# PX4FMUlite_V0_4.net
KiCad netlist of a schematic drawn in EAGLE
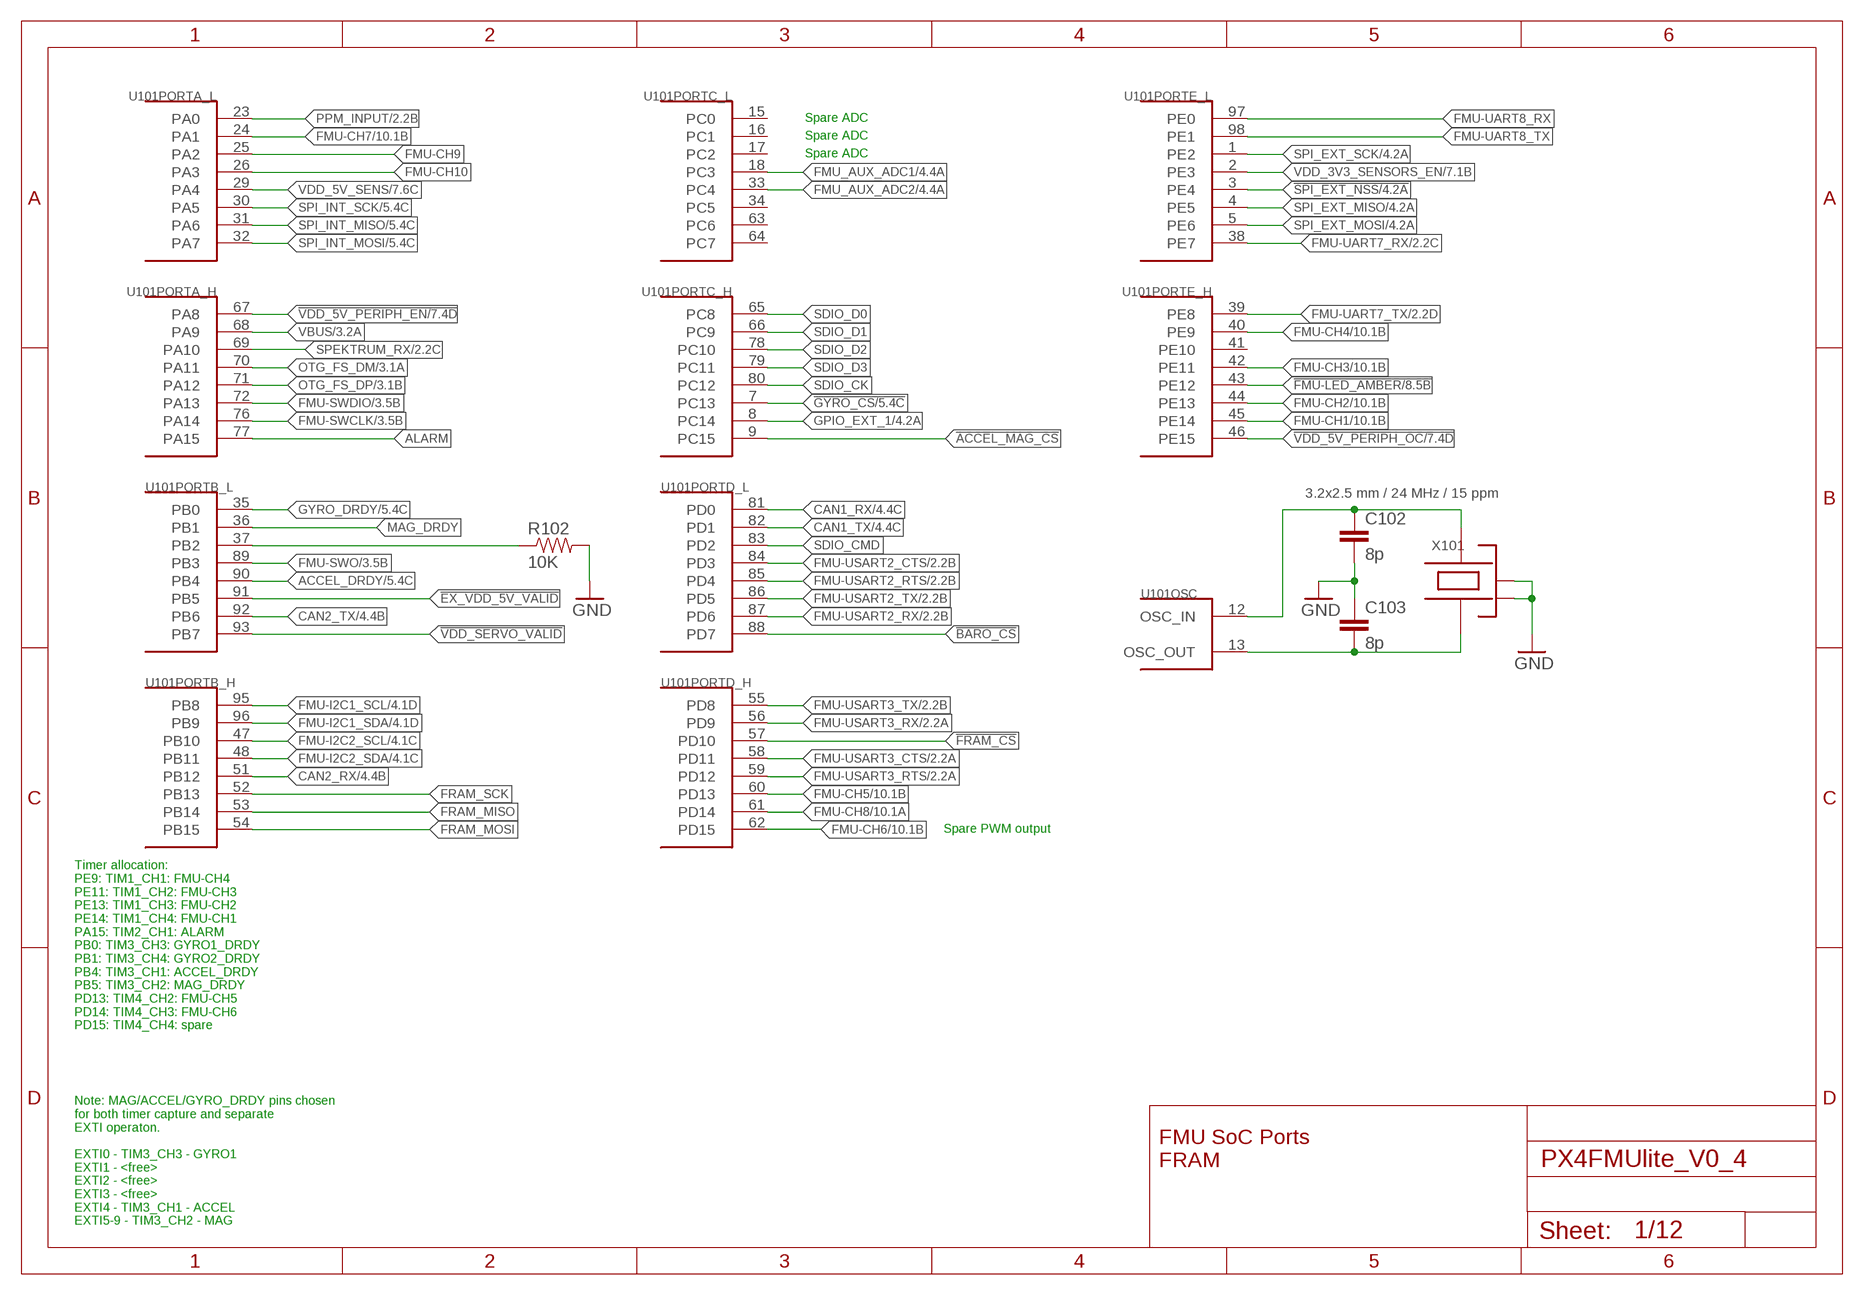
[diagram p0: schematic, sheet 1]
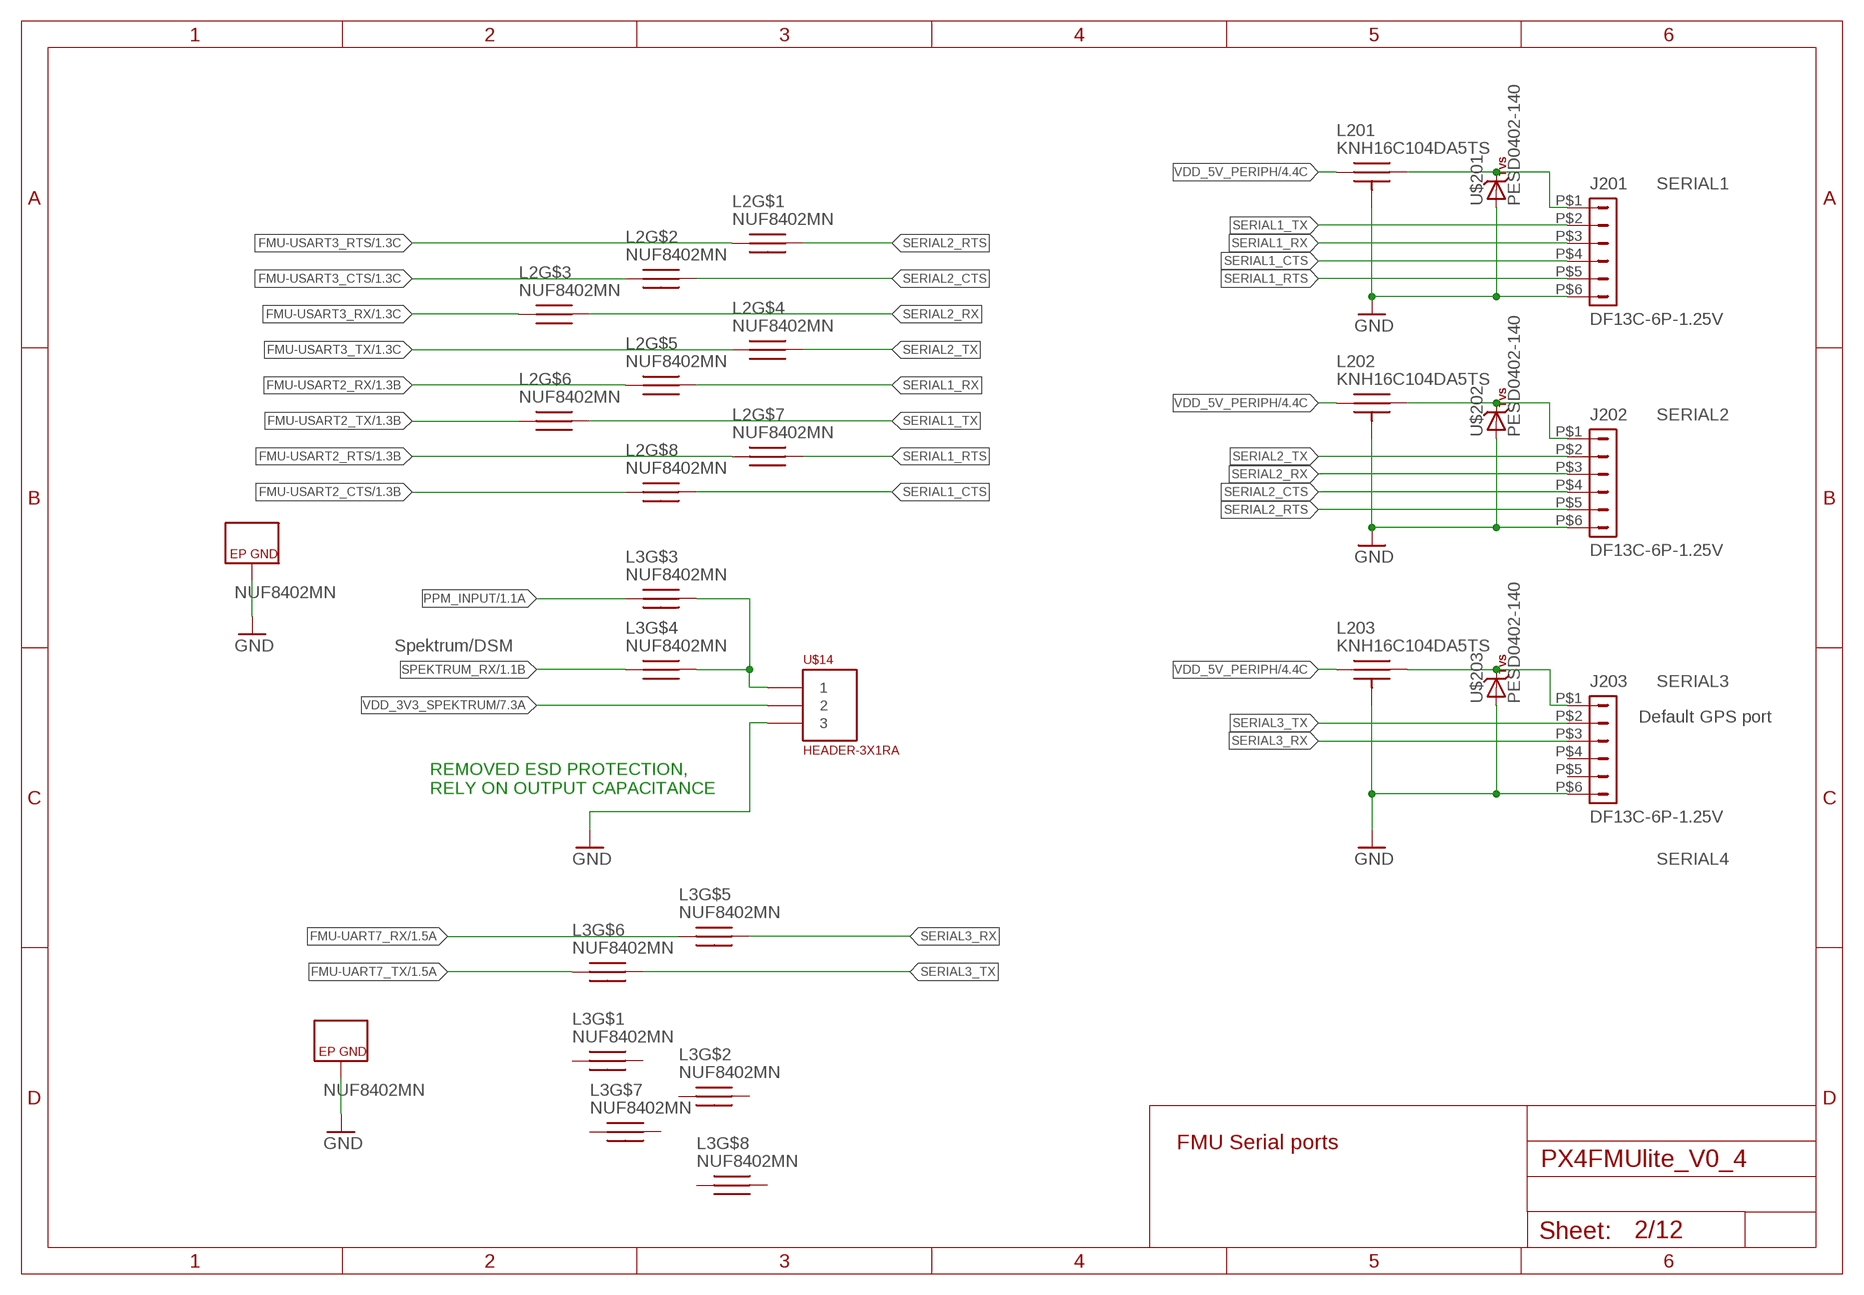
[diagram p1: schematic, sheet 2]
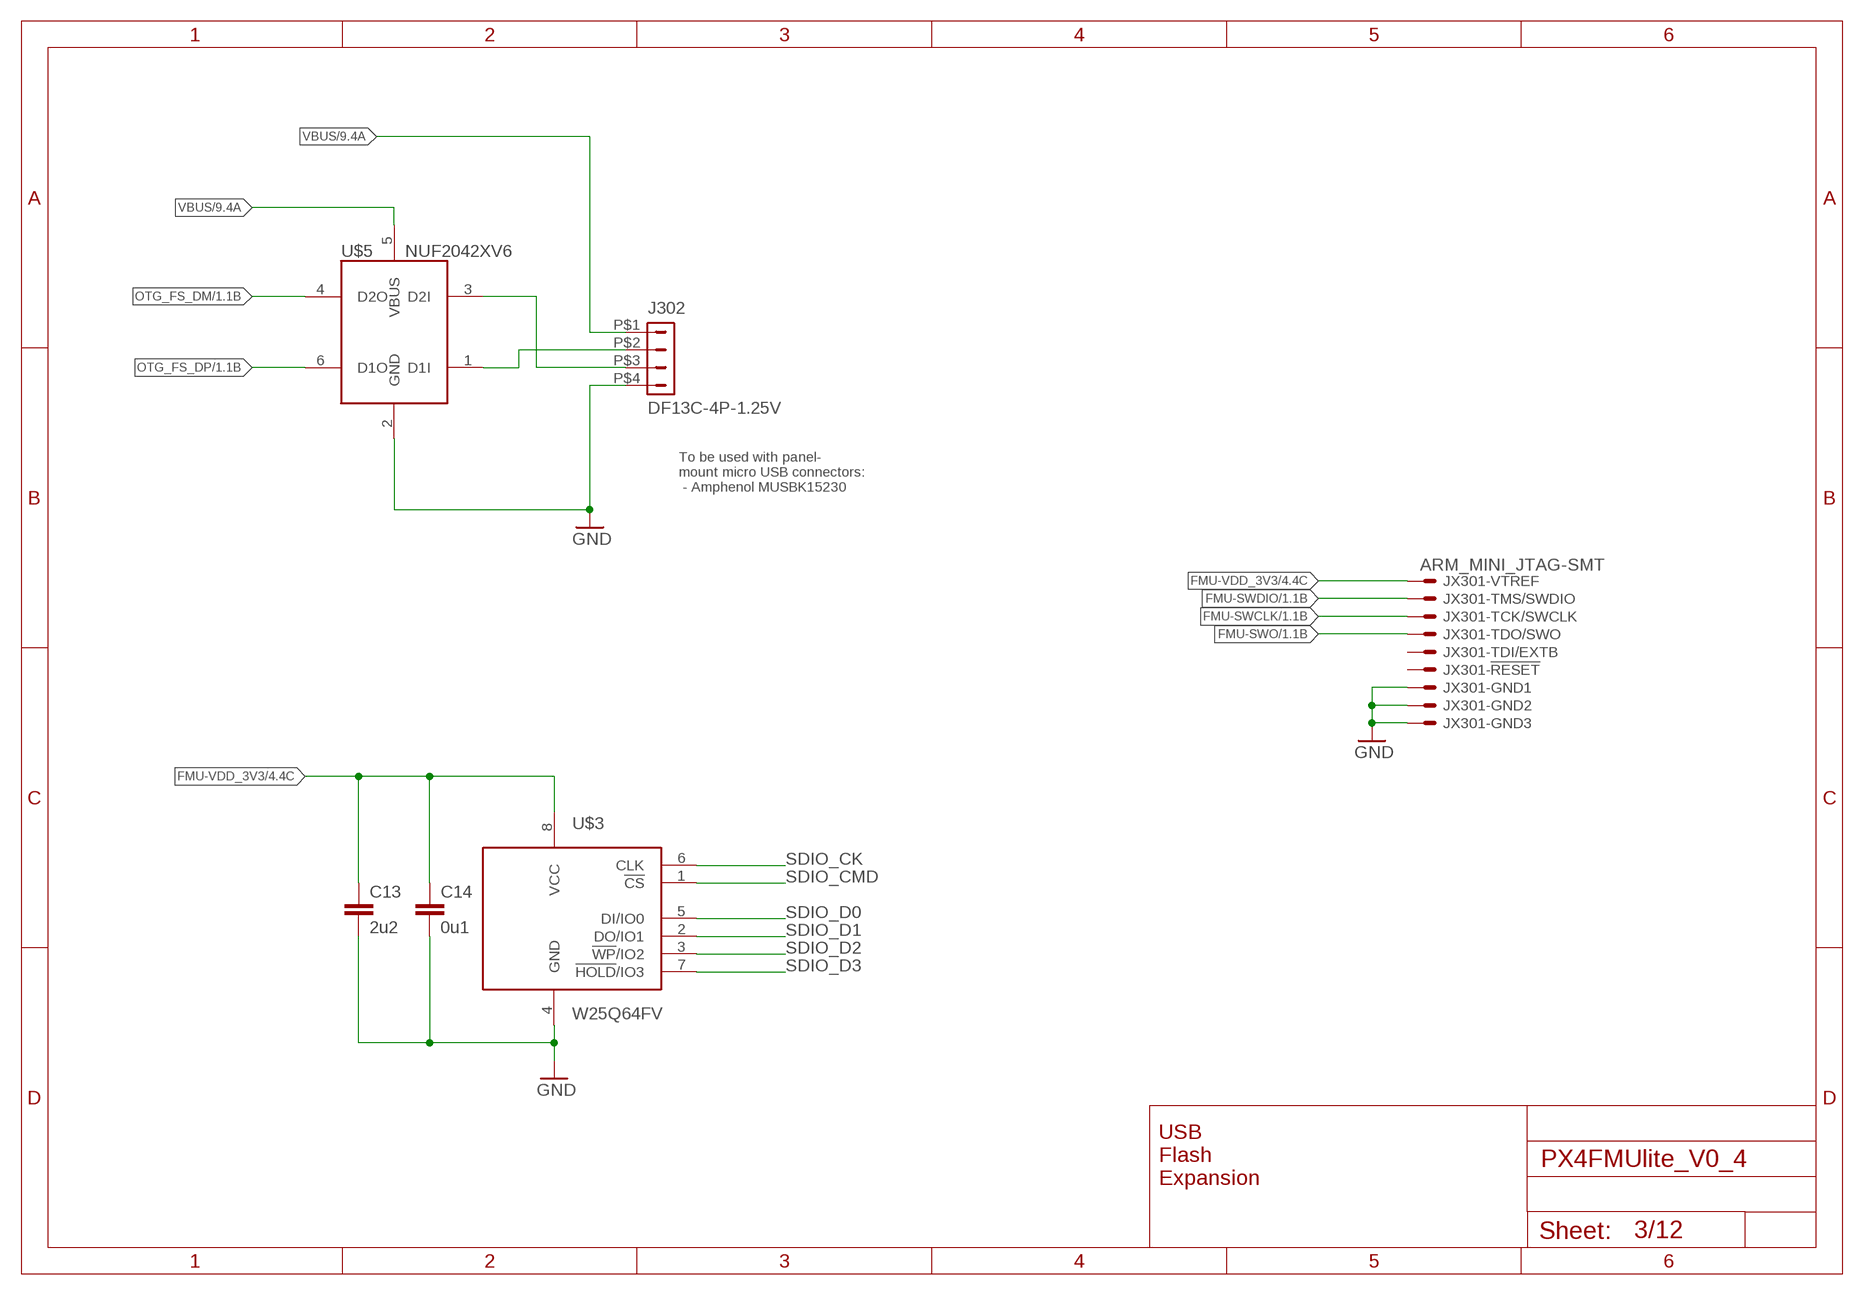
[diagram p2: schematic, sheet 3]
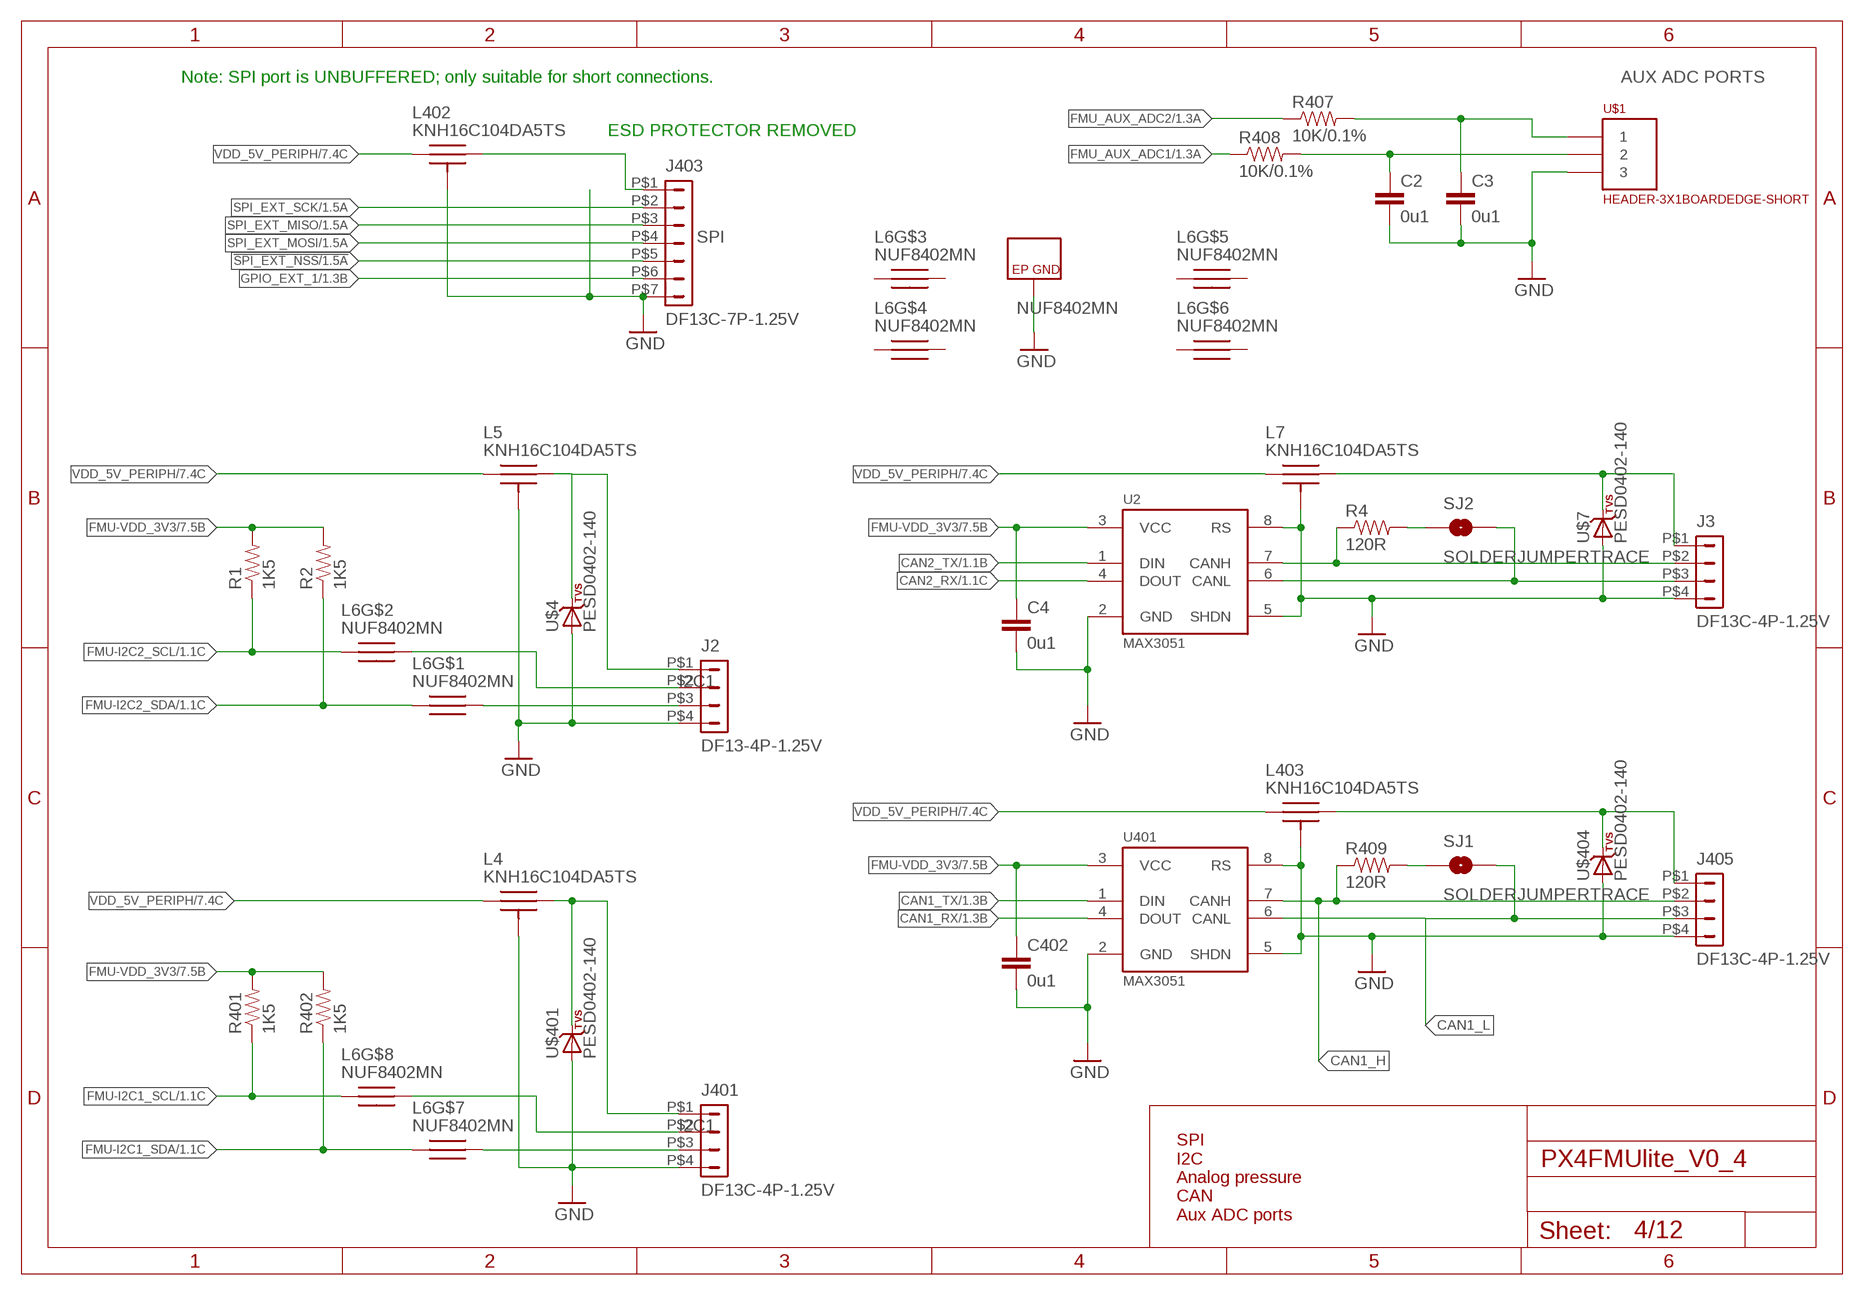
[diagram p3: schematic, sheet 4]
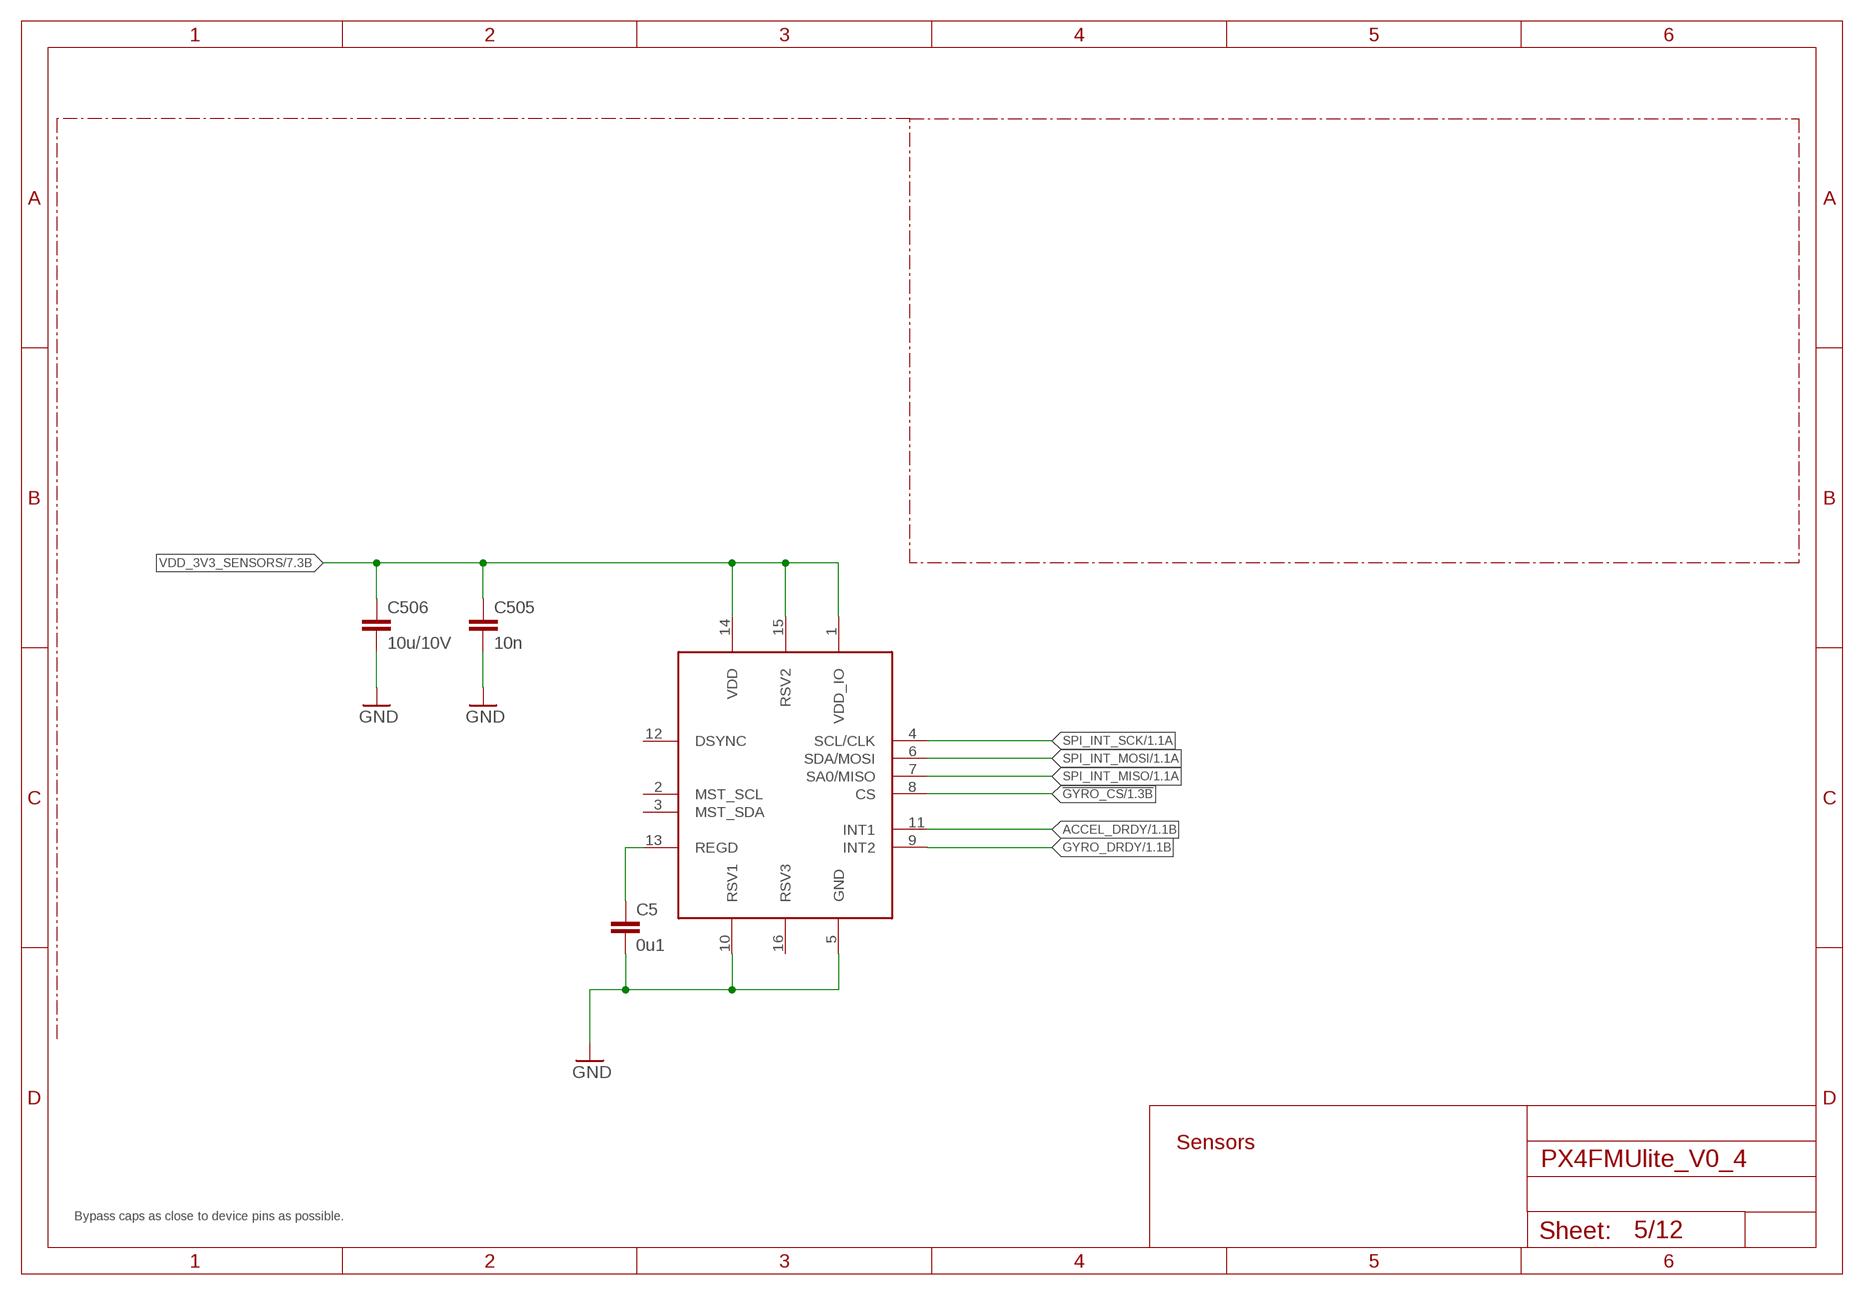
[diagram p4: schematic, sheet 5]
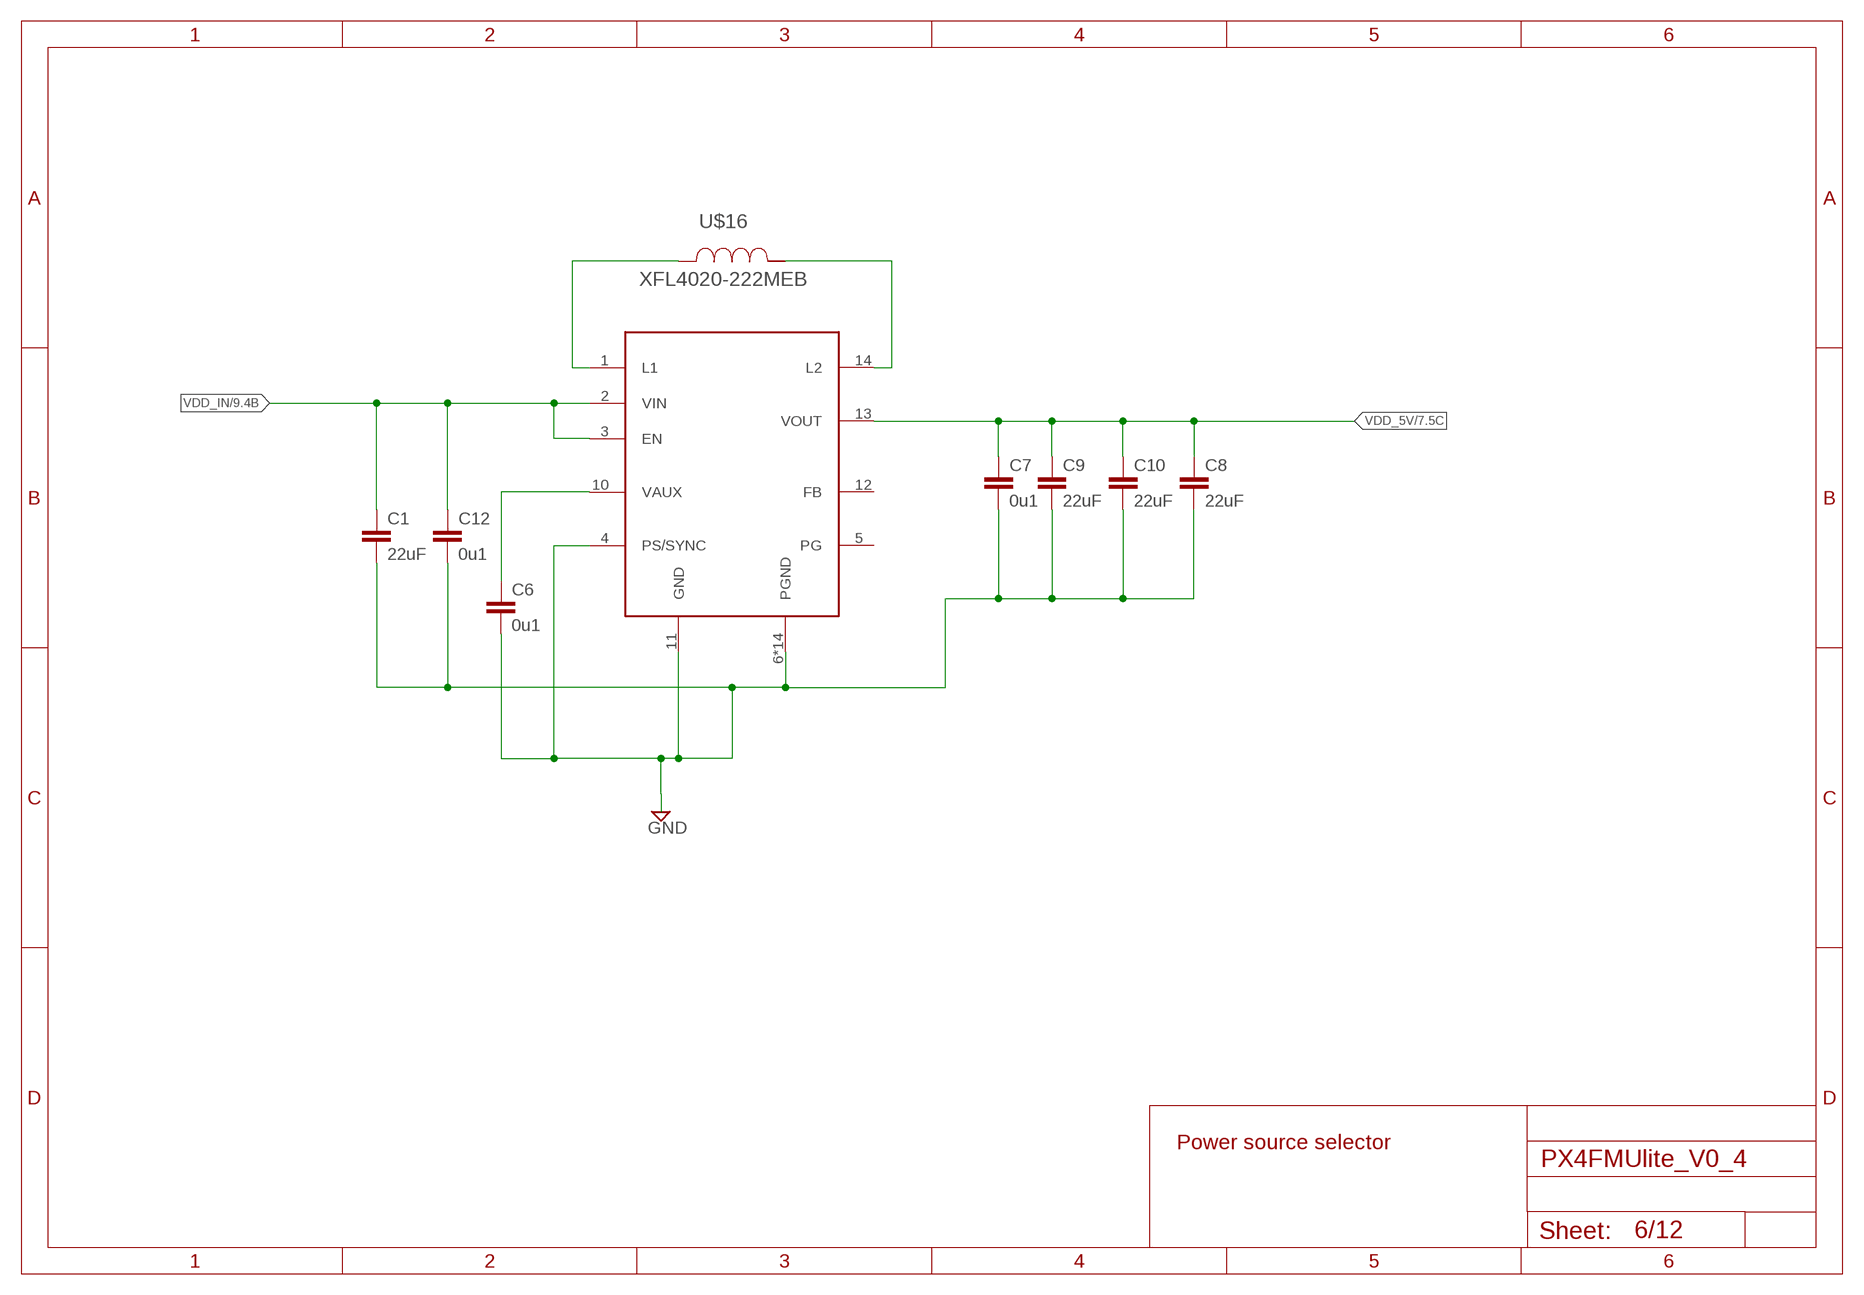
[diagram p5: schematic, sheet 6]
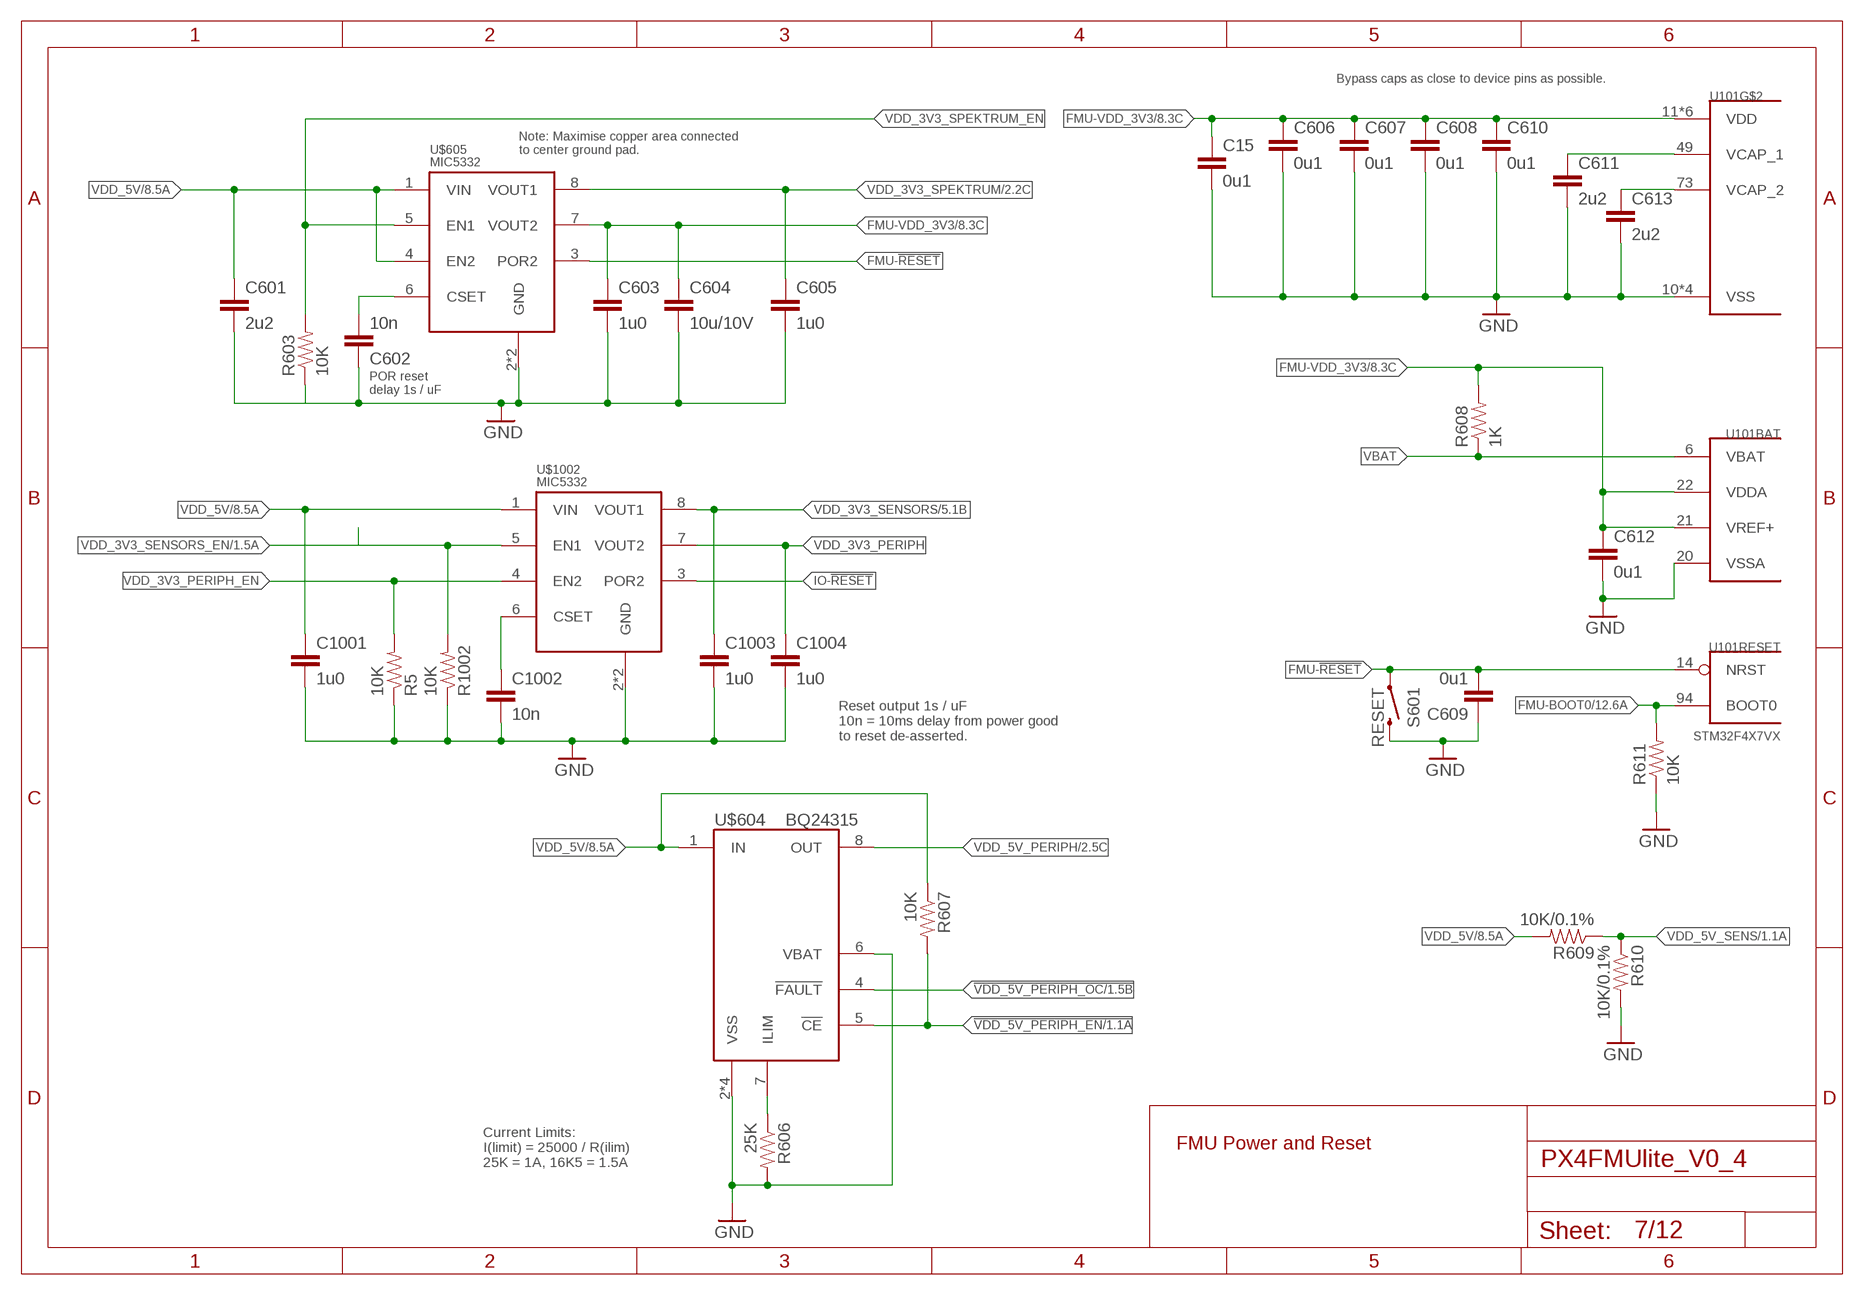
[diagram p6: schematic, sheet 7]
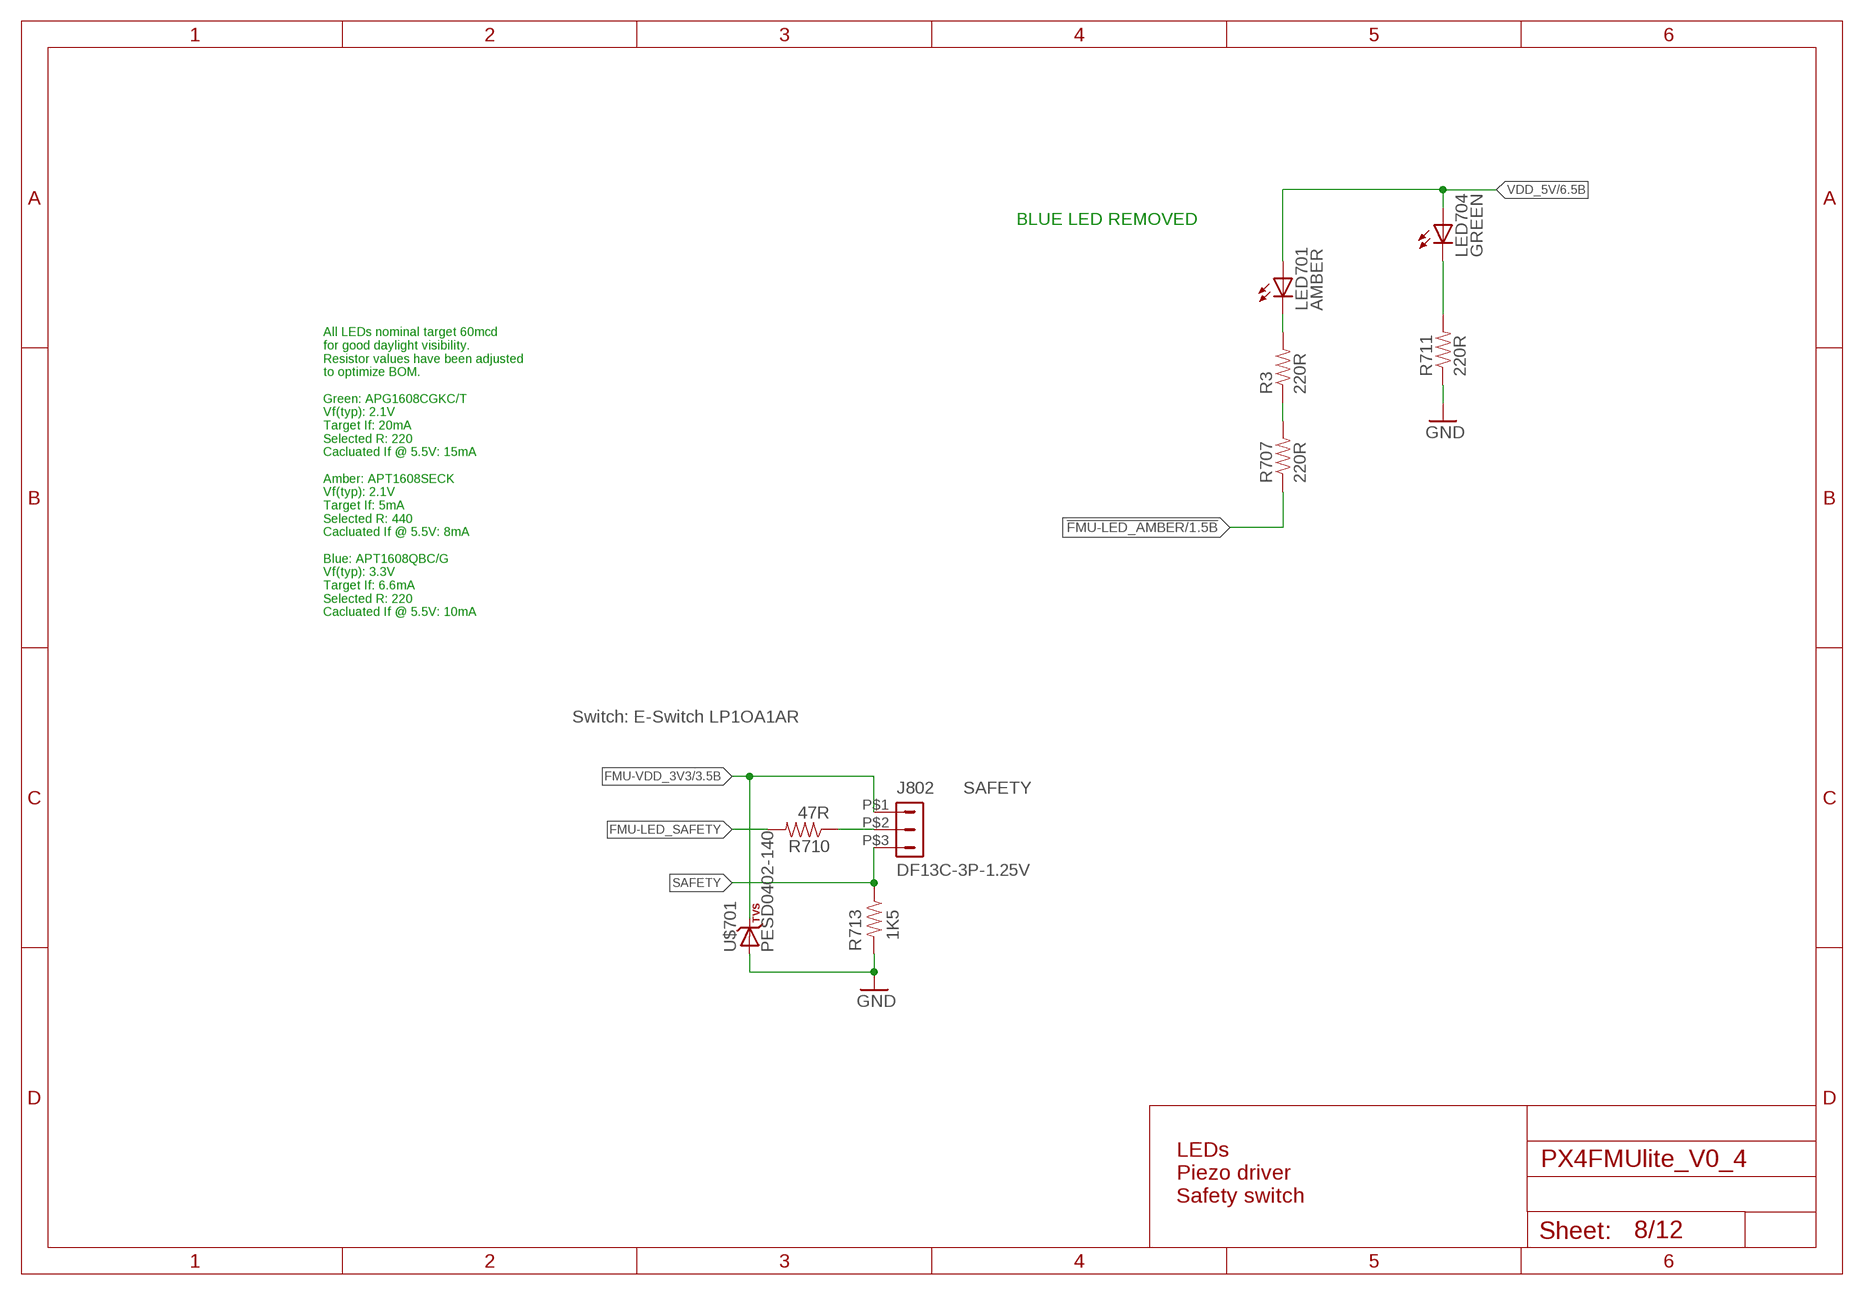
[diagram p7: schematic, sheet 8]
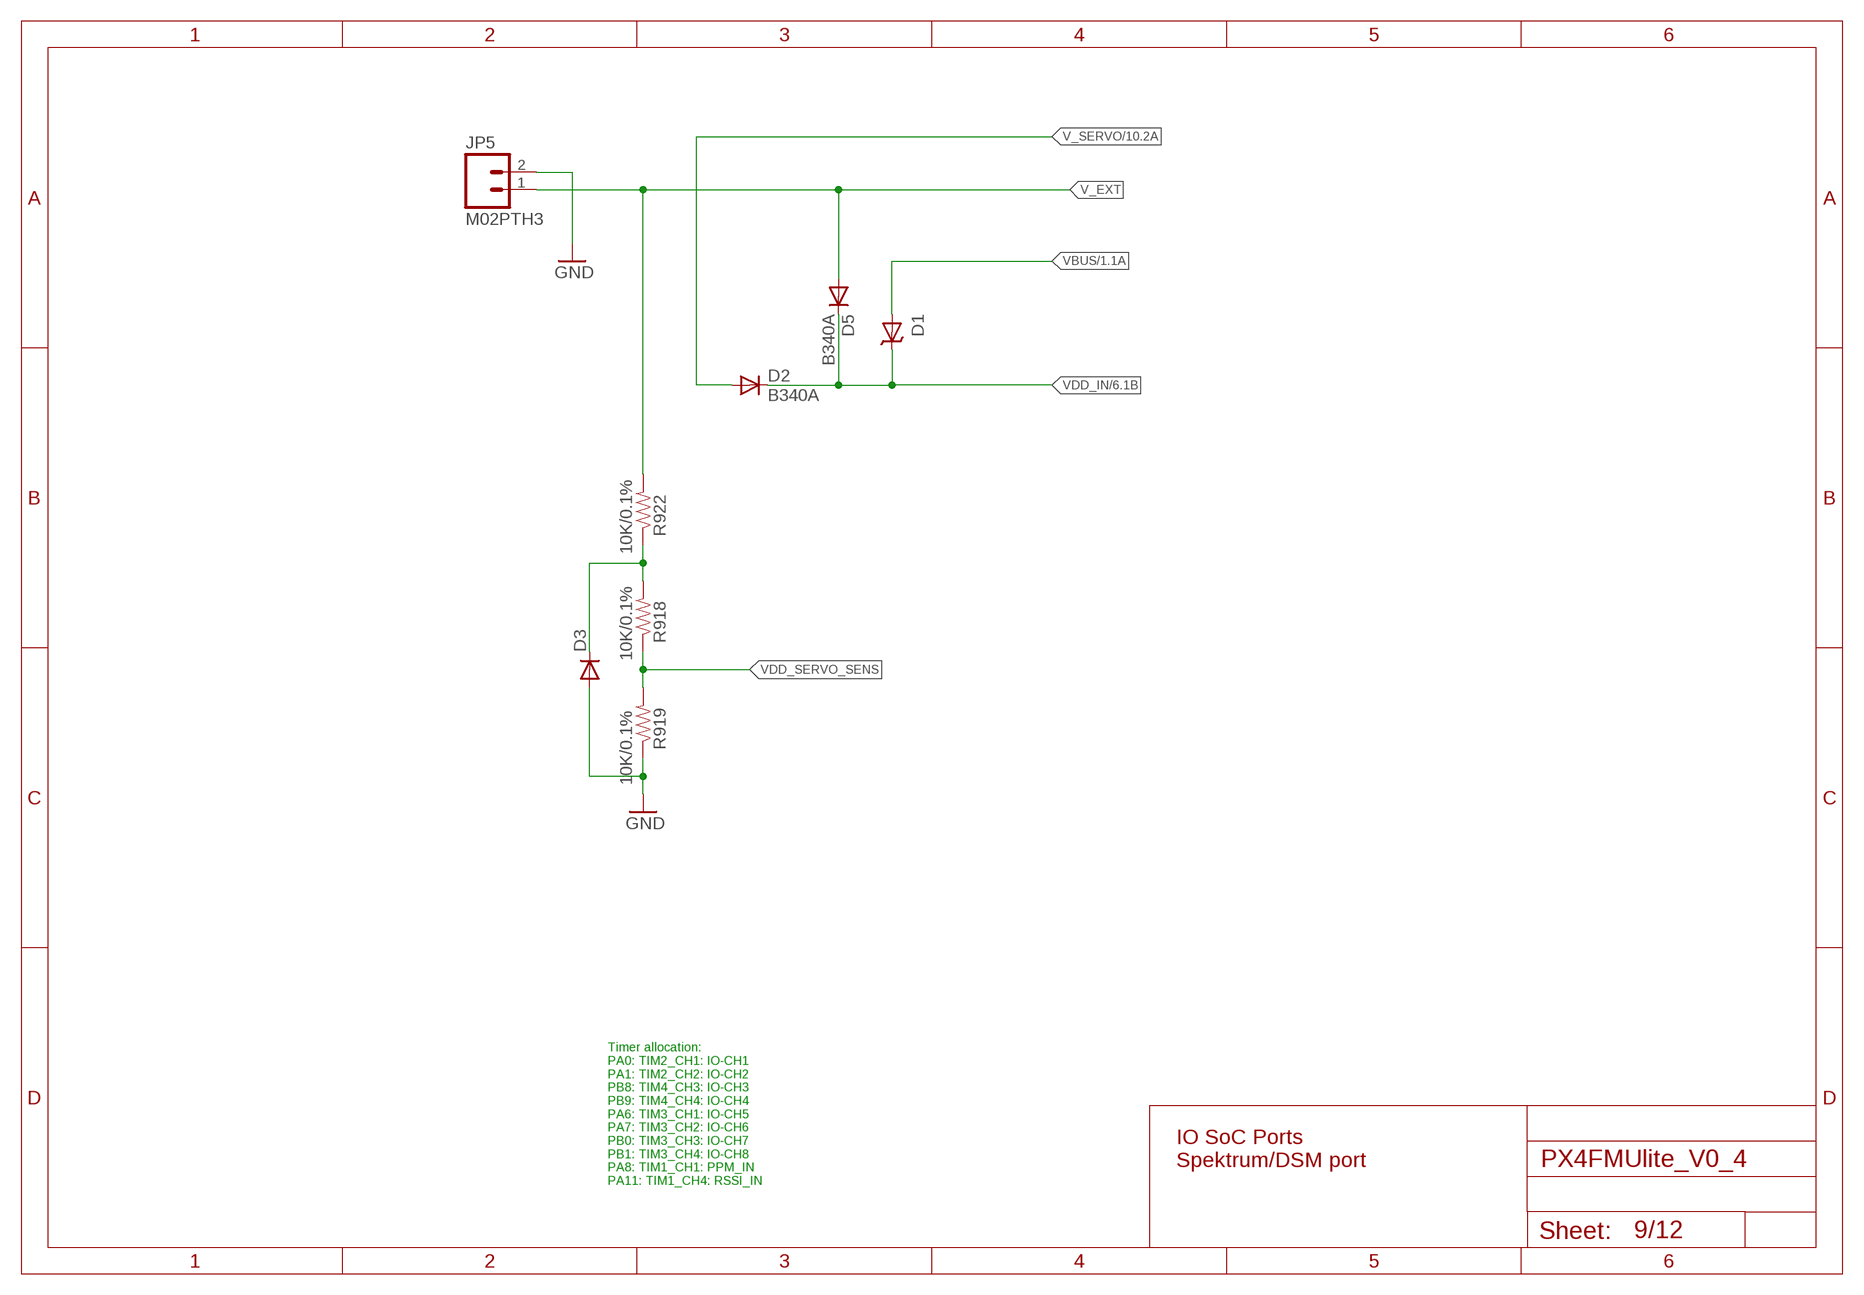
[diagram p8: schematic, sheet 9]
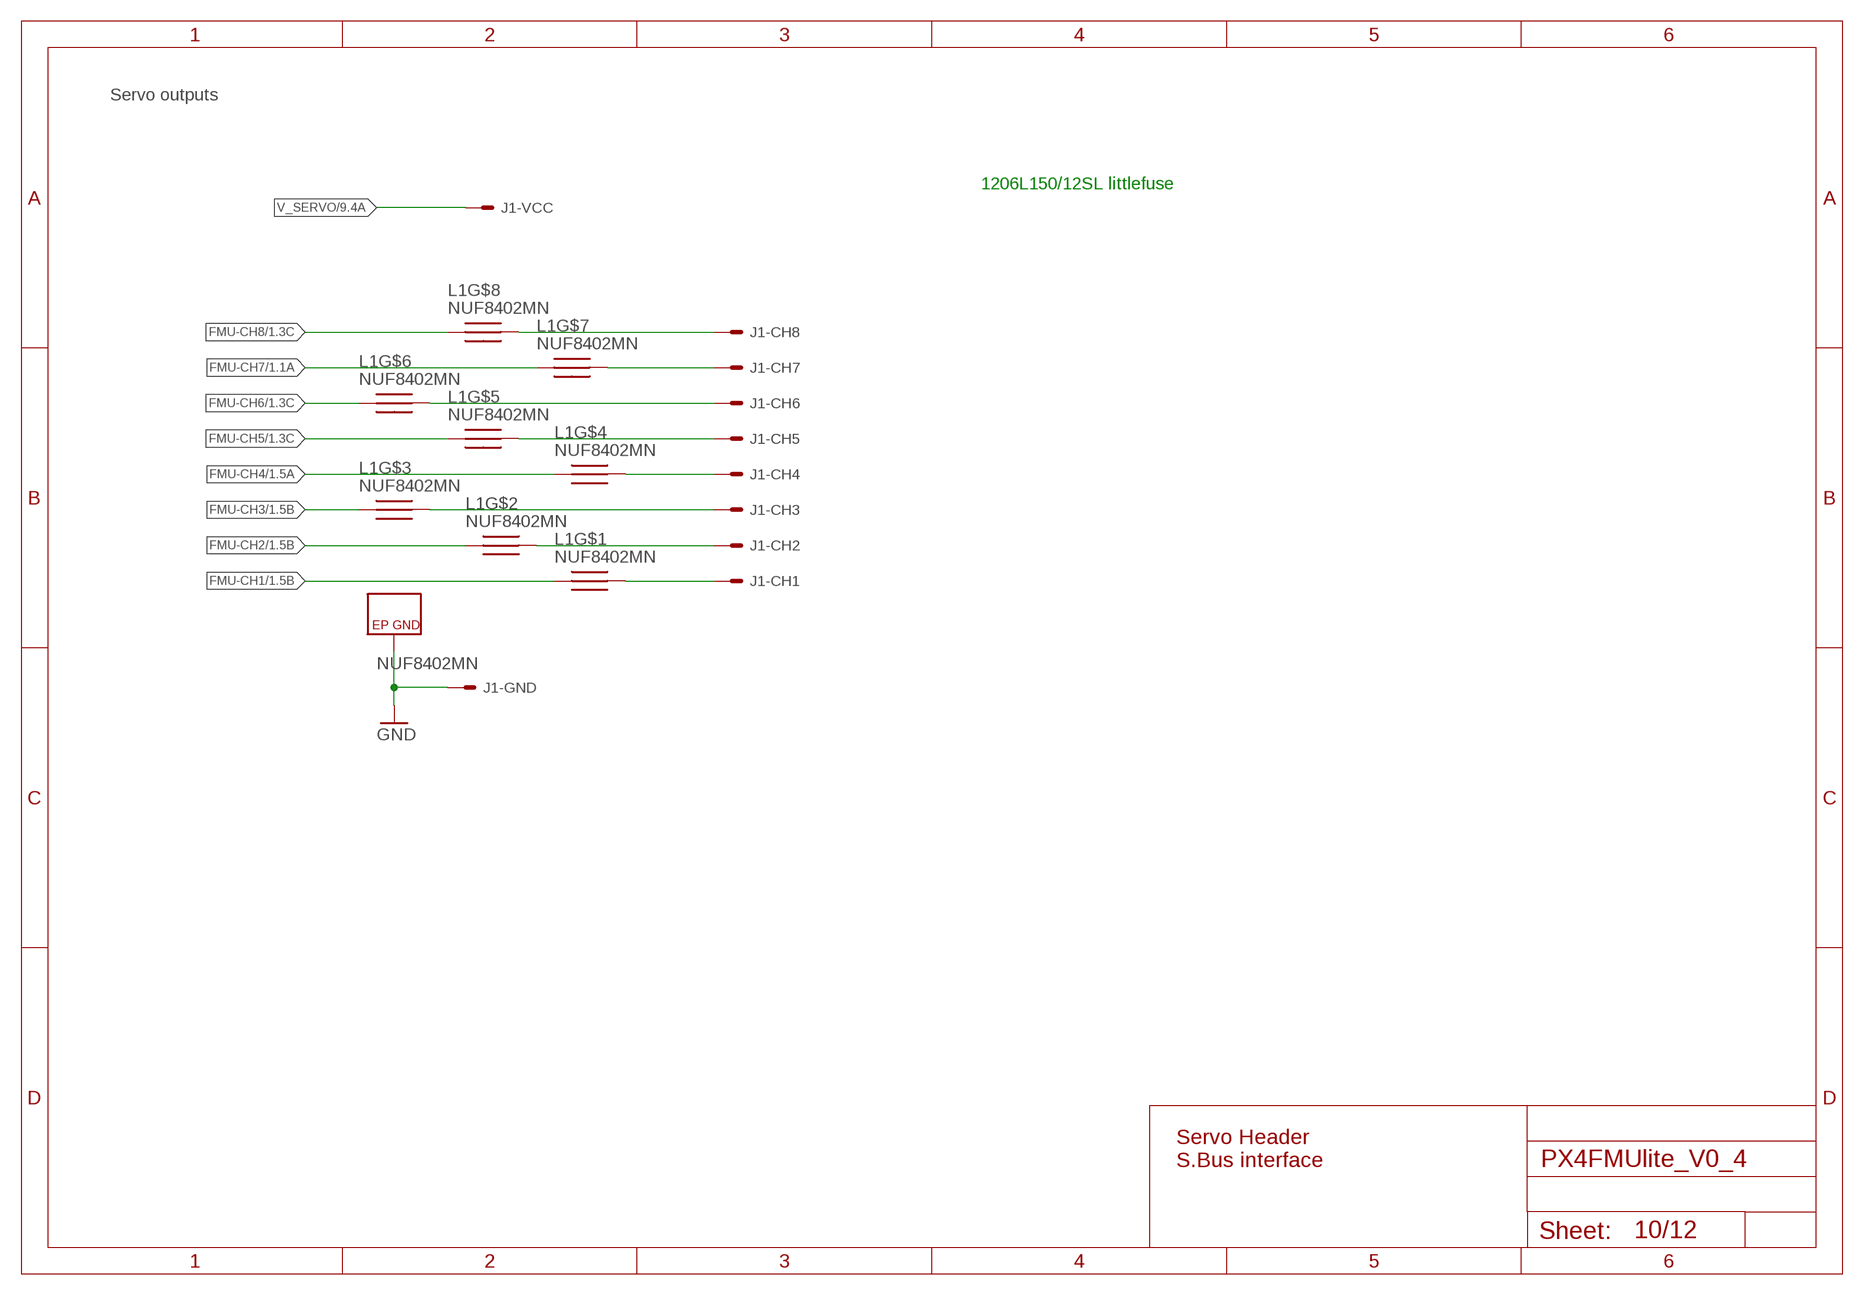
[diagram p9: schematic, sheet 10]
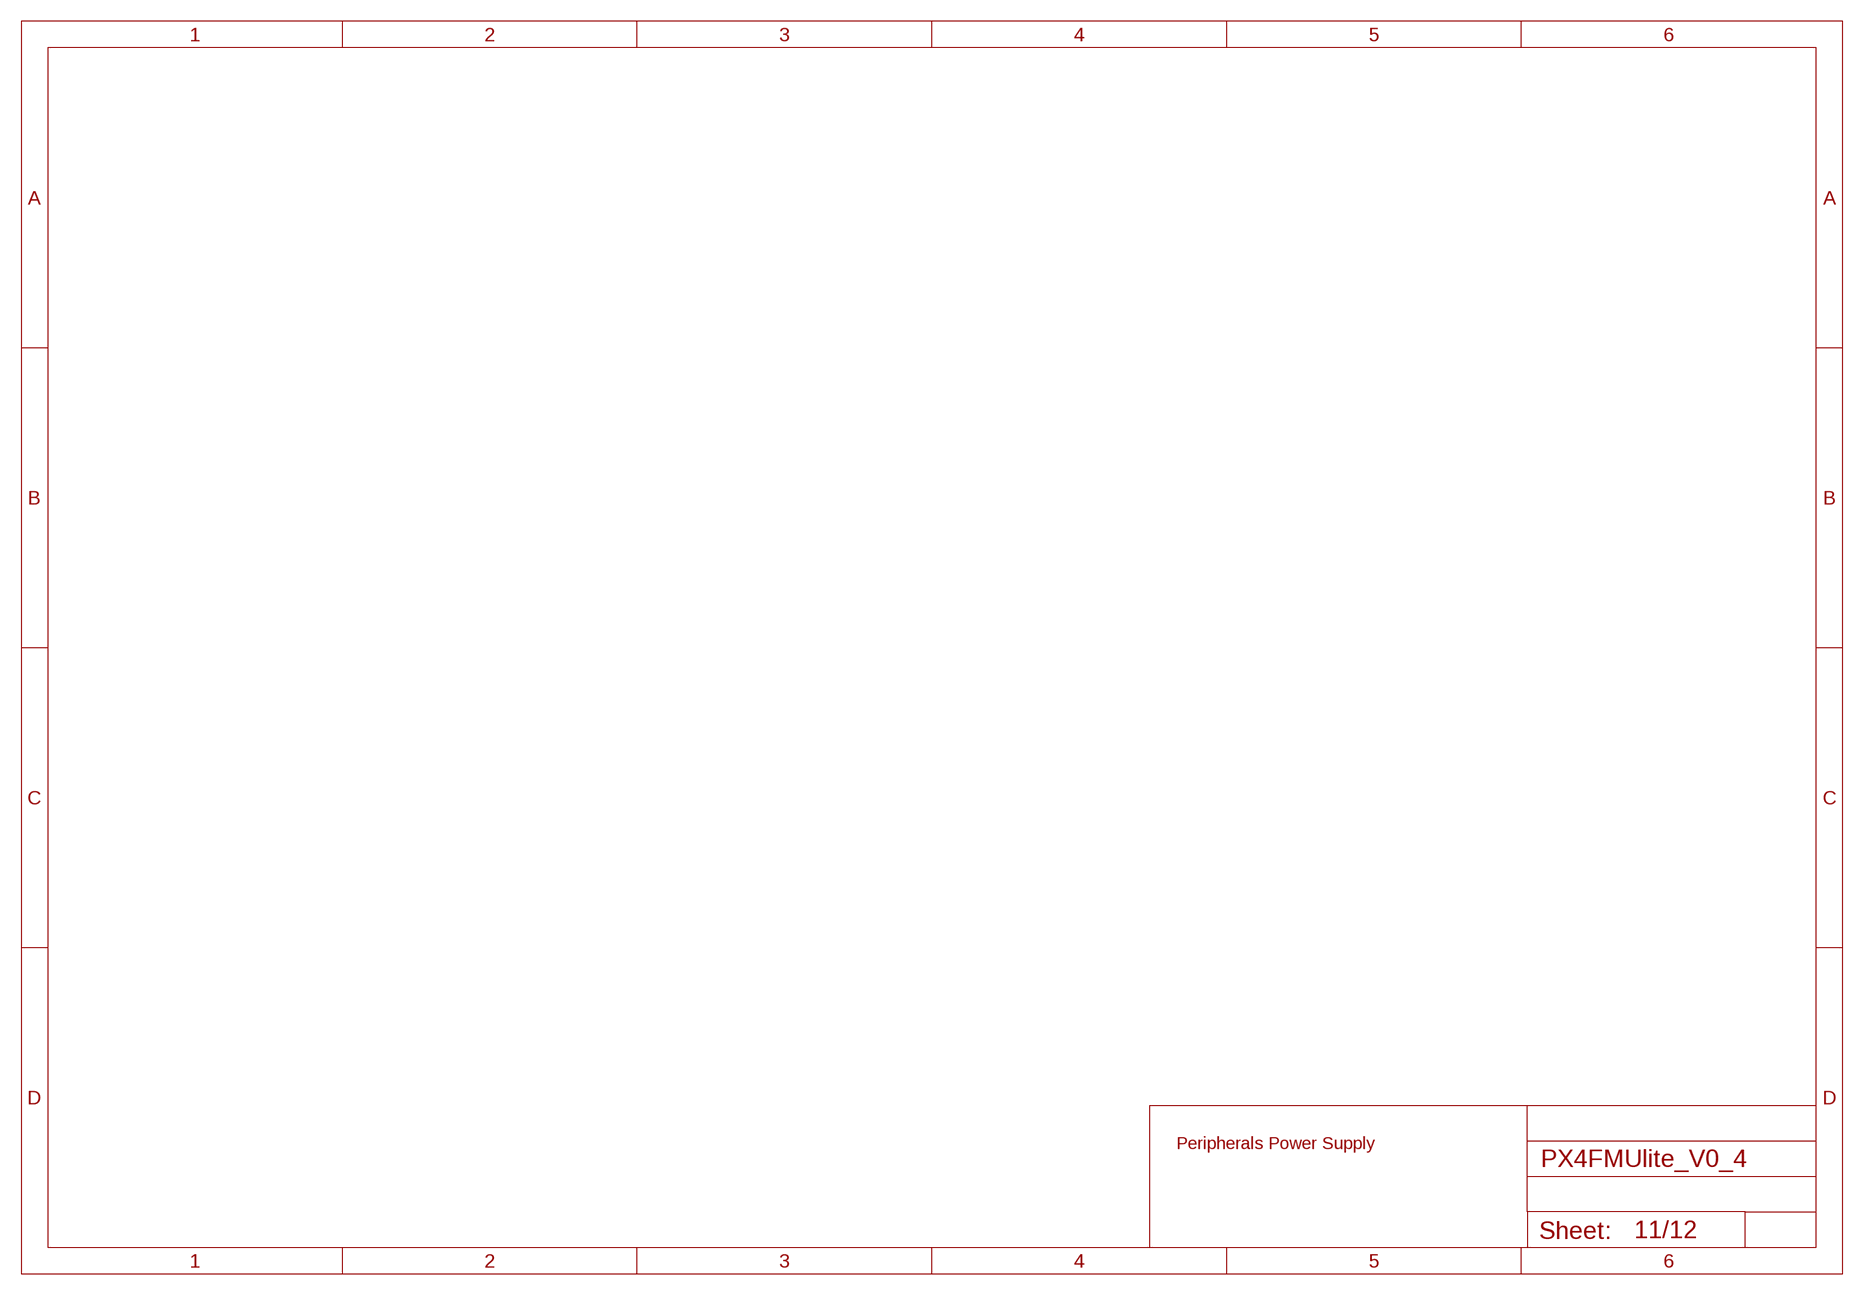
[diagram p10: schematic, sheet 11]
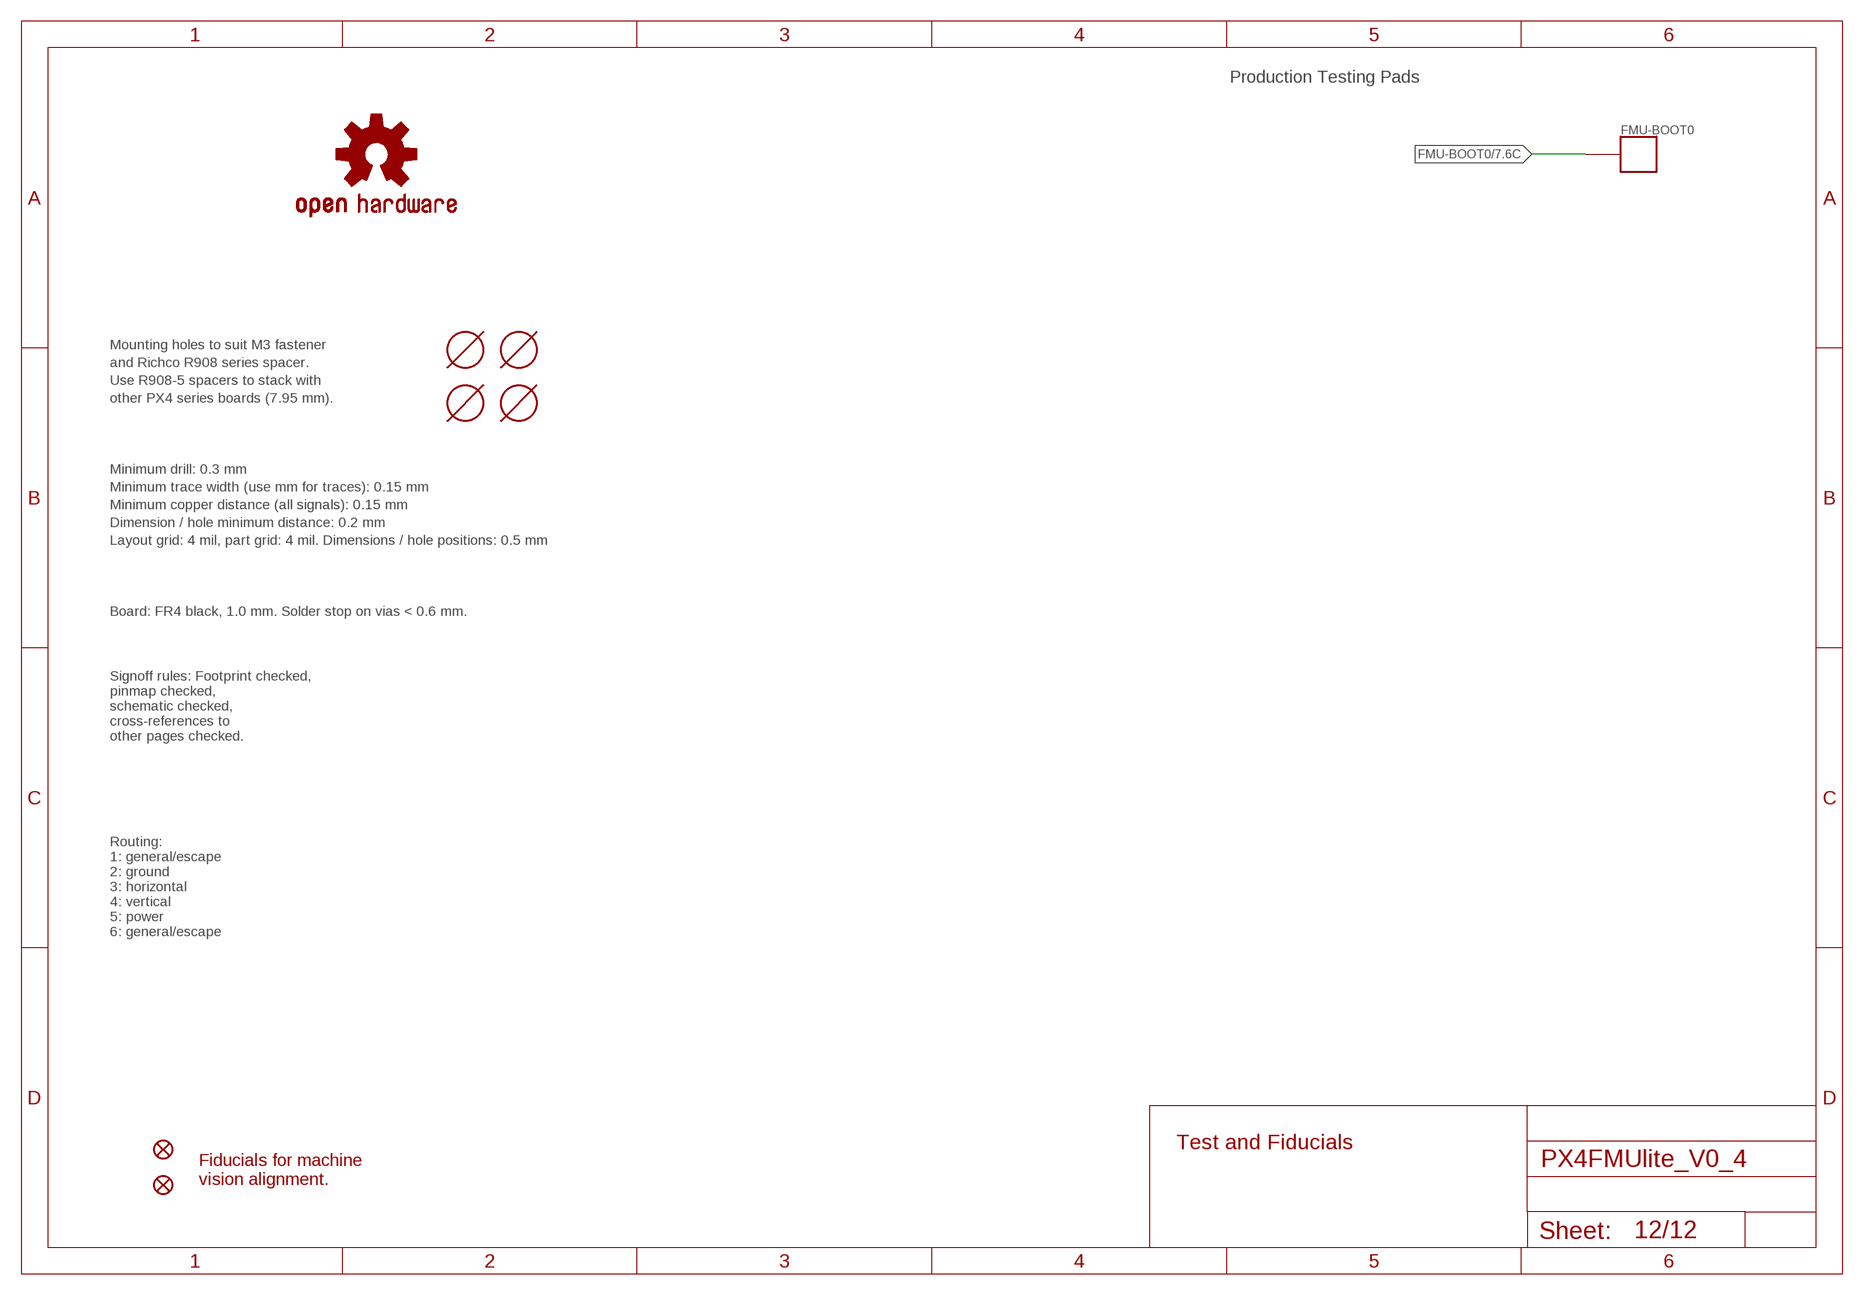
[diagram p11: schematic, sheet 12]

(export (version "E")
  (design (tool "Eeschema 10.0.6"))
  (components
    (comp (ref "J1")
      (value "SERVO_HEADER-3X8")
      (footprint "eagle-import:3X8RA_SERVO")
      (libsource (lib "eagle-import") (part "SERVO_HEADER-3X8"))
    )
    (comp (ref "L1")
      (value "NUF8402MN")
      (footprint "eagle-import:DFN16-THIN")
      (libsource (lib "eagle-import") (part "NUF8402MN"))
    )
    (comp (ref "C15")
      (value "0u1")
      (footprint "eagle-import:0402-CAP")
      (fields (field (name "PARTNO") "CC0402ZRY5V7BB104"))
      (libsource (lib "eagle-import") (part "CAP0402"))
    )
    (comp (ref "C601")
      (value "2u2")
      (footprint "eagle-import:0603-CAP")
      (fields (field (name "PARTNO") "C1608Y5V1C225Z"))
      (libsource (lib "eagle-import") (part "CAP0603"))
    )
    (comp (ref "C602")
      (value "10n")
      (footprint "eagle-import:0402-CAP")
      (fields (field (name "PARTNO") "CC0402KRX7R7BB103"))
      (libsource (lib "eagle-import") (part "CAP0402"))
    )
    (comp (ref "C603")
      (value "1u0")
      (footprint "eagle-import:0603-CAP")
      (fields (field (name "PARTNO") "CC0603ZRY5V7BB105"))
      (libsource (lib "eagle-import") (part "CAP0603"))
    )
    (comp (ref "C604")
      (value "10u/10V")
      (footprint "eagle-import:0805-CAP")
      (fields (field (name "PARTNO") "CC0805ZKY5V6BB106"))
      (libsource (lib "eagle-import") (part "CAP0805"))
    )
    (comp (ref "C605")
      (value "1u0")
      (footprint "eagle-import:0603-CAP")
      (fields (field (name "PARTNO") "CC0603ZRY5V7BB105"))
      (libsource (lib "eagle-import") (part "CAP0603"))
    )
    (comp (ref "C606")
      (value "0u1")
      (footprint "eagle-import:0402-CAP")
      (fields (field (name "PARTNO") "CC0402ZRY5V7BB104"))
      (libsource (lib "eagle-import") (part "CAP0402"))
    )
    (comp (ref "C607")
      (value "0u1")
      (footprint "eagle-import:0402-CAP")
      (fields (field (name "PARTNO") "CC0402ZRY5V7BB104"))
      (libsource (lib "eagle-import") (part "CAP0402"))
    )
    (comp (ref "C608")
      (value "0u1")
      (footprint "eagle-import:0402-CAP")
      (fields (field (name "PARTNO") "CC0402ZRY5V7BB104"))
      (libsource (lib "eagle-import") (part "CAP0402"))
    )
    (comp (ref "C609")
      (value "0u1")
      (footprint "eagle-import:0402-CAP")
      (fields (field (name "PARTNO") "CC0402ZRY5V7BB104"))
      (libsource (lib "eagle-import") (part "CAP0402"))
    )
    (comp (ref "C610")
      (value "0u1")
      (footprint "eagle-import:0402-CAP")
      (fields (field (name "PARTNO") "CC0402ZRY5V7BB104"))
      (libsource (lib "eagle-import") (part "CAP0402"))
    )
    (comp (ref "C611")
      (value "2u2")
      (footprint "eagle-import:0603-CAP")
      (fields (field (name "PARTNO") "C1608Y5V1C225Z"))
      (libsource (lib "eagle-import") (part "CAP0603"))
    )
    (comp (ref "C612")
      (value "0u1")
      (footprint "eagle-import:0402-CAP")
      (fields (field (name "PARTNO") "CC0402ZRY5V7BB104"))
      (libsource (lib "eagle-import") (part "CAP0402"))
    )
    (comp (ref "C613")
      (value "2u2")
      (footprint "eagle-import:0603-CAP")
      (fields (field (name "PARTNO") "C1608Y5V1C225Z"))
      (libsource (lib "eagle-import") (part "CAP0603"))
    )
    (comp (ref "C1001")
      (value "1u0")
      (footprint "eagle-import:0603-CAP")
      (fields (field (name "PARTNO") "CC0603ZRY5V7BB105"))
      (libsource (lib "eagle-import") (part "CAP0603"))
    )
    (comp (ref "C1002")
      (value "10n")
      (footprint "eagle-import:0402-CAP")
      (fields (field (name "PARTNO") "CC0402KRX7R7BB103"))
      (libsource (lib "eagle-import") (part "CAP0402"))
    )
    (comp (ref "C1003")
      (value "1u0")
      (footprint "eagle-import:0603-CAP")
      (fields (field (name "PARTNO") "CC0603ZRY5V7BB105"))
      (libsource (lib "eagle-import") (part "CAP0603"))
    )
    (comp (ref "C1004")
      (value "1u0")
      (footprint "eagle-import:0603-CAP")
      (fields (field (name "PARTNO") "CC0603ZRY5V7BB105"))
      (libsource (lib "eagle-import") (part "CAP0603"))
    )
    (comp (ref "R5")
      (value "10K")
      (footprint "eagle-import:0402-RES")
      (fields (field (name "PARTNO") "RC0402FR-0710KL"))
      (libsource (lib "eagle-import") (part "RESISTOR0402-RES"))
    )
    (comp (ref "R603")
      (value "10K")
      (footprint "eagle-import:0402-RES")
      (fields (field (name "PARTNO") "RC0402FR-0710KL"))
      (libsource (lib "eagle-import") (part "RESISTOR0402-RES"))
    )
    (comp (ref "R606")
      (value "25K")
      (footprint "eagle-import:0402-RES")
      (fields (field (name "PARTNO") "RMCF0402FT25K5"))
      (libsource (lib "eagle-import") (part "RESISTOR0402-RES"))
    )
    (comp (ref "R607")
      (value "10K")
      (footprint "eagle-import:0402-RES")
      (fields (field (name "PARTNO") "RC0402FR-0710KL"))
      (libsource (lib "eagle-import") (part "RESISTOR0402-RES"))
    )
    (comp (ref "R608")
      (value "1K")
      (footprint "eagle-import:0402-RES")
      (fields (field (name "PARTNO") "RC0402FR-071KL"))
      (libsource (lib "eagle-import") (part "RESISTOR0402-RES"))
    )
    (comp (ref "R609")
      (value "10K/0.1%")
      (footprint "eagle-import:0402-RES")
      (fields (field (name "PARTNO") "ERA-2AEB103X"))
      (libsource (lib "eagle-import") (part "RESISTOR0402-RES"))
    )
    (comp (ref "R610")
      (value "10K/0.1%")
      (footprint "eagle-import:0402-RES")
      (fields (field (name "PARTNO") "ERA-2AEB103X"))
      (libsource (lib "eagle-import") (part "RESISTOR0402-RES"))
    )
    (comp (ref "R611")
      (value "10K")
      (footprint "eagle-import:0402-RES")
      (fields (field (name "PARTNO") "RC0402FR-0710KL"))
      (libsource (lib "eagle-import") (part "RESISTOR0402-RES"))
    )
    (comp (ref "R1002")
      (value "10K")
      (footprint "eagle-import:0402-RES")
      (fields (field (name "PARTNO") "RC0402FR-0710KL"))
      (libsource (lib "eagle-import") (part "RESISTOR0402-RES"))
    )
    (comp (ref "S601")
      (value "RESET")
      (footprint "eagle-import:EVQP7J01K")
      (fields (field (name "PARTNO") "EVQP7J01K"))
      (libsource (lib "eagle-import") (part "SWITCH-MOMENTARY-2"))
    )
    (comp (ref "U$604")
      (value "BQ24315")
      (footprint "eagle-import:QFN8-DSG")
      (fields (field (name "PARTNO") "BQ24315DSGR"))
      (libsource (lib "eagle-import") (part "BQ24315"))
    )
    (comp (ref "U$605")
      (value "MIC5332")
      (footprint "eagle-import:MLF-8-EPAD")
      (fields (field (name "PARTNO") "MIC5332-SSYMT"))
      (libsource (lib "eagle-import") (part "MIC5332"))
    )
    (comp (ref "U$1002")
      (value "MIC5332")
      (footprint "eagle-import:MLF-8-EPAD")
      (fields (field (name "PARTNO") "MIC5332-SSYMT"))
      (libsource (lib "eagle-import") (part "MIC5332"))
    )
    (comp (ref "U101")
      (value "STM32F4X7VX")
      (footprint "eagle-import:TQFP100")
      (fields (field (name "PARTNO") "STM32F427VI"))
      (libsource (lib "eagle-import") (part "STM32F4X7VX"))
    )
    (comp (ref "FMU-BOOT0")
      (value "PAD.04")
      (footprint "eagle-import:PAD.04X.04")
      (libsource (lib "eagle-import") (part "PAD.04"))
    )
    (comp (ref "JP1")
      (value "FIDUCIAL1.5X3")
      (footprint "eagle-import:FIDUCIAL-1.5X3")
      (libsource (lib "eagle-import") (part "FIDUCIAL1.5X3"))
    )
    (comp (ref "JP2")
      (value "FIDUCIAL1.5X3")
      (footprint "eagle-import:FIDUCIAL-1.5X3")
      (libsource (lib "eagle-import") (part "FIDUCIAL1.5X3"))
    )
    (comp (ref "M3_MOUNT1101")
      (value "MOUNT-HOLE3.1MM")
      (footprint "eagle-import:MOUNT-HOLE3.1")
      (libsource (lib "eagle-import") (part "MOUNT-HOLE3.1MM"))
    )
    (comp (ref "M3_MOUNT1102")
      (value "MOUNT-HOLE3.1MM")
      (footprint "eagle-import:MOUNT-HOLE3.1")
      (libsource (lib "eagle-import") (part "MOUNT-HOLE3.1MM"))
    )
    (comp (ref "M3_MOUNT1103")
      (value "MOUNT-HOLE3.1MM")
      (footprint "eagle-import:MOUNT-HOLE3.1")
      (libsource (lib "eagle-import") (part "MOUNT-HOLE3.1MM"))
    )
    (comp (ref "M3_MOUNT1104")
      (value "MOUNT-HOLE3.1MM")
      (footprint "eagle-import:MOUNT-HOLE3.1")
      (libsource (lib "eagle-import") (part "MOUNT-HOLE3.1MM"))
    )
    (comp (ref "OSHW_LOGO")
      (value "OSHW-LOGOS")
      (footprint "eagle-import:OSHW-LOGO-S")
      (libsource (lib "eagle-import") (part "OSHW-LOGOS"))
    )
    (comp (ref "J201")
      (value "DF13C-6P-1.25V")
      (footprint "eagle-import:DF13C-6P-1.25V")
      (fields (field (name "PARTNO") "DF13C-6P-1.25V(20)"))
      (libsource (lib "eagle-import") (part "DF13-6P-1.25V"))
    )
    (comp (ref "J202")
      (value "DF13C-6P-1.25V")
      (footprint "eagle-import:DF13C-6P-1.25V")
      (fields (field (name "PARTNO") "DF13C-6P-1.25V(20)"))
      (libsource (lib "eagle-import") (part "DF13-6P-1.25V"))
    )
    (comp (ref "J203")
      (value "DF13C-6P-1.25V")
      (footprint "eagle-import:DF13C-6P-1.25V")
      (fields (field (name "PARTNO") "DF13C-6P-1.25V(20)"))
      (libsource (lib "eagle-import") (part "DF13-6P-1.25V"))
    )
    (comp (ref "L2")
      (value "NUF8402MN")
      (footprint "eagle-import:DFN16-THIN")
      (libsource (lib "eagle-import") (part "NUF8402MN"))
    )
    (comp (ref "L3")
      (value "NUF8402MN")
      (footprint "eagle-import:DFN16-THIN")
      (libsource (lib "eagle-import") (part "NUF8402MN"))
    )
    (comp (ref "L201")
      (value "KNH16C104DA5TS")
      (footprint "eagle-import:KYOCERA-KNH16-DA")
      (libsource (lib "eagle-import") (part "KNH16C104DA5TS"))
    )
    (comp (ref "L202")
      (value "KNH16C104DA5TS")
      (footprint "eagle-import:KYOCERA-KNH16-DA")
      (libsource (lib "eagle-import") (part "KNH16C104DA5TS"))
    )
    (comp (ref "L203")
      (value "KNH16C104DA5TS")
      (footprint "eagle-import:KYOCERA-KNH16-DA")
      (libsource (lib "eagle-import") (part "KNH16C104DA5TS"))
    )
    (comp (ref "U$14")
      (value "HEADER-3X1RA")
      (footprint "eagle-import:3X1RA")
      (libsource (lib "eagle-import") (part "HEADER-3X1RA"))
    )
    (comp (ref "U$201")
      (value "PESD0402-140")
      (footprint "eagle-import:0402-TVS")
      (libsource (lib "eagle-import") (part "DIODE-TVS"))
    )
    (comp (ref "U$202")
      (value "PESD0402-140")
      (footprint "eagle-import:0402-TVS")
      (libsource (lib "eagle-import") (part "DIODE-TVS"))
    )
    (comp (ref "U$203")
      (value "PESD0402-140")
      (footprint "eagle-import:0402-TVS")
      (libsource (lib "eagle-import") (part "DIODE-TVS"))
    )
    (comp (ref "D1")
      (value "MSS1P4-M3")
      (footprint "eagle-import:MICROSMP")
      (fields (field (name "PARTNO") "MSS1P4-M3/89A"))
      (libsource (lib "eagle-import") (part "DIODE-SCHOTTKY_MSMP"))
    )
    (comp (ref "D2")
      (value "B340A")
      (footprint "eagle-import:SMA-DIODE")
      (libsource (lib "eagle-import") (part "DIODESMA"))
    )
    (comp (ref "D3")
      (value "DIODESOD")
      (footprint "eagle-import:SOD-323")
      (libsource (lib "eagle-import") (part "DIODESOD"))
    )
    (comp (ref "D5")
      (value "B340A")
      (footprint "eagle-import:SMA-DIODE")
      (libsource (lib "eagle-import") (part "DIODESMA"))
    )
    (comp (ref "JP5")
      (value "M02PTH3")
      (footprint "eagle-import:1X02_LONGPADS")
      (libsource (lib "eagle-import") (part "M02PTH3"))
    )
    (comp (ref "R918")
      (value "10K/0.1%")
      (footprint "eagle-import:0402-RES")
      (fields (field (name "PARTNO") "ERA-2AEB103X"))
      (libsource (lib "eagle-import") (part "RESISTOR0402-RES"))
    )
    (comp (ref "R919")
      (value "10K/0.1%")
      (footprint "eagle-import:0402-RES")
      (fields (field (name "PARTNO") "ERA-2AEB103X"))
      (libsource (lib "eagle-import") (part "RESISTOR0402-RES"))
    )
    (comp (ref "R922")
      (value "10K/0.1%")
      (footprint "eagle-import:0402-RES")
      (fields (field (name "PARTNO") "ERA-2AEB103X"))
      (libsource (lib "eagle-import") (part "RESISTOR0402-RES"))
    )
    (comp (ref "C5")
      (value "0u1")
      (footprint "eagle-import:0402-CAP")
      (fields (field (name "PARTNO") "CC0402ZRY5V7BB104"))
      (libsource (lib "eagle-import") (part "CAP0402"))
    )
    (comp (ref "C505")
      (value "10n")
      (footprint "eagle-import:0402-CAP")
      (fields (field (name "PARTNO") "CC0402KRX7R7BB103"))
      (libsource (lib "eagle-import") (part "CAP0402"))
    )
    (comp (ref "C506")
      (value "10u/10V")
      (footprint "eagle-import:0805-CAP")
      (fields (field (name "PARTNO") "CC0805ZKY5V6BB106"))
      (libsource (lib "eagle-import") (part "CAP0805"))
    )
    (comp (ref "U$2")
      (value "MAX21100")
      (footprint "eagle-import:16LGA-3X3")
      (libsource (lib "eagle-import") (part "MAX21100"))
    )
    (comp (ref "C1")
      (value "22uF")
      (footprint "eagle-import:1210")
      (libsource (lib "eagle-import") (part "22UF-16V-20%-(1210)"))
    )
    (comp (ref "C6")
      (value "0u1")
      (footprint "eagle-import:0402-CAP")
      (fields (field (name "PARTNO") "CC0402ZRY5V7BB104"))
      (libsource (lib "eagle-import") (part "CAP0402"))
    )
    (comp (ref "C7")
      (value "0u1")
      (footprint "eagle-import:0402-CAP")
      (fields (field (name "PARTNO") "CC0402ZRY5V7BB104"))
      (libsource (lib "eagle-import") (part "CAP0402"))
    )
    (comp (ref "C8")
      (value "22uF")
      (footprint "eagle-import:1210")
      (libsource (lib "eagle-import") (part "22UF-16V-20%-(1210)"))
    )
    (comp (ref "C9")
      (value "22uF")
      (footprint "eagle-import:1210")
      (libsource (lib "eagle-import") (part "22UF-16V-20%-(1210)"))
    )
    (comp (ref "C10")
      (value "22uF")
      (footprint "eagle-import:1210")
      (libsource (lib "eagle-import") (part "22UF-16V-20%-(1210)"))
    )
    (comp (ref "C12")
      (value "0u1")
      (footprint "eagle-import:0402-CAP")
      (fields (field (name "PARTNO") "CC0402ZRY5V7BB104"))
      (libsource (lib "eagle-import") (part "CAP0402"))
    )
    (comp (ref "U$15")
      (value "TPS6303X")
      (footprint "eagle-import:PWSON10")
      (libsource (lib "eagle-import") (part "TPS6303X"))
    )
    (comp (ref "U$16")
      (value "XFL4020-222MEB")
      (footprint "eagle-import:XFL4020")
      (libsource (lib "eagle-import") (part "XFL4020-222MEB"))
    )
    (comp (ref "C2")
      (value "0u1")
      (footprint "eagle-import:0402-CAP")
      (fields (field (name "PARTNO") "CC0402ZRY5V7BB104"))
      (libsource (lib "eagle-import") (part "CAP0402"))
    )
    (comp (ref "C3")
      (value "0u1")
      (footprint "eagle-import:0402-CAP")
      (fields (field (name "PARTNO") "CC0402ZRY5V7BB104"))
      (libsource (lib "eagle-import") (part "CAP0402"))
    )
    (comp (ref "C4")
      (value "0u1")
      (footprint "eagle-import:0402-CAP")
      (fields (field (name "PARTNO") "CC0402ZRY5V7BB104"))
      (libsource (lib "eagle-import") (part "CAP0402"))
    )
    (comp (ref "C402")
      (value "0u1")
      (footprint "eagle-import:0402-CAP")
      (fields (field (name "PARTNO") "CC0402ZRY5V7BB104"))
      (libsource (lib "eagle-import") (part "CAP0402"))
    )
    (comp (ref "J2")
      (value "DF13-4P-1.25V")
      (footprint "eagle-import:DF13C-4P-1.25V")
      (fields (field (name "PARTNO") "DF13C-4P-1.25V(20)"))
      (libsource (lib "eagle-import") (part "DF13-4P-1.25V"))
    )
    (comp (ref "J3")
      (value "DF13C-4P-1.25V")
      (footprint "eagle-import:DF13C-4P-1.25V")
      (fields (field (name "PARTNO") "DF13C-4P-1.25V(20)"))
      (libsource (lib "eagle-import") (part "DF13-4P-1.25V"))
    )
    (comp (ref "J401")
      (value "DF13C-4P-1.25V")
      (footprint "eagle-import:DF13C-4P-1.25V")
      (fields (field (name "PARTNO") "DF13C-4P-1.25V(20)"))
      (libsource (lib "eagle-import") (part "DF13-4P-1.25V"))
    )
    (comp (ref "J403")
      (value "DF13C-7P-1.25V")
      (footprint "eagle-import:DF13C-7P-1.25V")
      (fields (field (name "PARTNO") "DF13C-7P-1.25V(20)"))
      (libsource (lib "eagle-import") (part "DF13-7P-1.25V"))
    )
    (comp (ref "J405")
      (value "DF13C-4P-1.25V")
      (footprint "eagle-import:DF13C-4P-1.25V")
      (fields (field (name "PARTNO") "DF13C-4P-1.25V(20)"))
      (libsource (lib "eagle-import") (part "DF13-4P-1.25V"))
    )
    (comp (ref "L4")
      (value "KNH16C104DA5TS")
      (footprint "eagle-import:KYOCERA-KNH16-DA")
      (libsource (lib "eagle-import") (part "KNH16C104DA5TS"))
    )
    (comp (ref "L5")
      (value "KNH16C104DA5TS")
      (footprint "eagle-import:KYOCERA-KNH16-DA")
      (libsource (lib "eagle-import") (part "KNH16C104DA5TS"))
    )
    (comp (ref "L6")
      (value "NUF8402MN")
      (footprint "eagle-import:DFN16-THIN")
      (libsource (lib "eagle-import") (part "NUF8402MN"))
    )
    (comp (ref "L7")
      (value "KNH16C104DA5TS")
      (footprint "eagle-import:KYOCERA-KNH16-DA")
      (libsource (lib "eagle-import") (part "KNH16C104DA5TS"))
    )
    (comp (ref "L402")
      (value "KNH16C104DA5TS")
      (footprint "eagle-import:KYOCERA-KNH16-DA")
      (libsource (lib "eagle-import") (part "KNH16C104DA5TS"))
    )
    (comp (ref "L403")
      (value "KNH16C104DA5TS")
      (footprint "eagle-import:KYOCERA-KNH16-DA")
      (libsource (lib "eagle-import") (part "KNH16C104DA5TS"))
    )
    (comp (ref "R1")
      (value "1K5")
      (footprint "eagle-import:0402-RES")
      (fields (field (name "PARTNO") "RC0402FR-071K5L"))
      (libsource (lib "eagle-import") (part "RESISTOR0402-RES"))
    )
    (comp (ref "R2")
      (value "1K5")
      (footprint "eagle-import:0402-RES")
      (fields (field (name "PARTNO") "RC0402FR-071K5L"))
      (libsource (lib "eagle-import") (part "RESISTOR0402-RES"))
    )
    (comp (ref "R4")
      (value "120R")
      (footprint "eagle-import:0402-RES")
      (fields (field (name "PARTNO") "RC0402FR-07120RL"))
      (libsource (lib "eagle-import") (part "RESISTOR0402-RES"))
    )
    (comp (ref "R401")
      (value "1K5")
      (footprint "eagle-import:0402-RES")
      (fields (field (name "PARTNO") "RC0402FR-071K5L"))
      (libsource (lib "eagle-import") (part "RESISTOR0402-RES"))
    )
    (comp (ref "R402")
      (value "1K5")
      (footprint "eagle-import:0402-RES")
      (fields (field (name "PARTNO") "RC0402FR-071K5L"))
      (libsource (lib "eagle-import") (part "RESISTOR0402-RES"))
    )
    (comp (ref "R407")
      (value "10K/0.1%")
      (footprint "eagle-import:0402-RES")
      (fields (field (name "PARTNO") "ERA-2AEB103X"))
      (libsource (lib "eagle-import") (part "RESISTOR0402-RES"))
    )
    (comp (ref "R408")
      (value "10K/0.1%")
      (footprint "eagle-import:0402-RES")
      (fields (field (name "PARTNO") "ERA-2AEB103X"))
      (libsource (lib "eagle-import") (part "RESISTOR0402-RES"))
    )
    (comp (ref "R409")
      (value "120R")
      (footprint "eagle-import:0402-RES")
      (fields (field (name "PARTNO") "RC0402FR-07120RL"))
      (libsource (lib "eagle-import") (part "RESISTOR0402-RES"))
    )
    (comp (ref "SJ1")
      (value "SOLDERJUMPERTRACE")
      (footprint "eagle-import:SJ_2S-TRACE")
      (libsource (lib "eagle-import") (part "SOLDERJUMPERTRACE"))
    )
    (comp (ref "SJ2")
      (value "SOLDERJUMPERTRACE")
      (footprint "eagle-import:SJ_2S-TRACE")
      (libsource (lib "eagle-import") (part "SOLDERJUMPERTRACE"))
    )
    (comp (ref "U$1")
      (value "HEADER-3X1BOARDEDGE-SHORT")
      (footprint "eagle-import:HEADER_3X01_SMD_H_BOARD_EDGE_SHORT")
      (libsource (lib "eagle-import") (part "HEADER-3X1BOARDEDGE-SHORT"))
    )
    (comp (ref "U$4")
      (value "PESD0402-140")
      (footprint "eagle-import:0402-TVS")
      (libsource (lib "eagle-import") (part "DIODE-TVS"))
    )
    (comp (ref "U$7")
      (value "PESD0402-140")
      (footprint "eagle-import:0402-TVS")
      (libsource (lib "eagle-import") (part "DIODE-TVS"))
    )
    (comp (ref "U$401")
      (value "PESD0402-140")
      (footprint "eagle-import:0402-TVS")
      (libsource (lib "eagle-import") (part "DIODE-TVS"))
    )
    (comp (ref "U$404")
      (value "PESD0402-140")
      (footprint "eagle-import:0402-TVS")
      (libsource (lib "eagle-import") (part "DIODE-TVS"))
    )
    (comp (ref "U2")
      (value "MAX3051")
      (footprint "eagle-import:SOT23-8")
      (fields (field (name "PARTNO") "MAX3051EKA"))
      (libsource (lib "eagle-import") (part "MAX3051MAX3051EKA"))
    )
    (comp (ref "U401")
      (value "MAX3051")
      (footprint "eagle-import:SOT23-8")
      (fields (field (name "PARTNO") "MAX3051EKA"))
      (libsource (lib "eagle-import") (part "MAX3051MAX3051EKA"))
    )
    (comp (ref "C13")
      (value "2u2")
      (footprint "eagle-import:0603-CAP")
      (fields (field (name "PARTNO") "C1608Y5V1C225Z"))
      (libsource (lib "eagle-import") (part "CAP0603"))
    )
    (comp (ref "C14")
      (value "0u1")
      (footprint "eagle-import:0402-CAP")
      (fields (field (name "PARTNO") "CC0402ZRY5V7BB104"))
      (libsource (lib "eagle-import") (part "CAP0402"))
    )
    (comp (ref "J302")
      (value "DF13C-4P-1.25V")
      (footprint "eagle-import:DF13C-4P-1.25V")
      (fields (field (name "PARTNO") "DF13C-4P-1.25V(20)"))
      (libsource (lib "eagle-import") (part "DF13-4P-1.25V"))
    )
    (comp (ref "JX301")
      (value "ARM_MINI_JTAG-SMT")
      (footprint "eagle-import:FTSH-105-01-XXX-DV-K")
      (fields (field (name "BOM") "EXCLUDE") (field (name "PARTNO") "M50-3900542"))
      (libsource (lib "eagle-import") (part "ARM_MINI_JTAG-SMT"))
    )
    (comp (ref "U$3")
      (value "W25Q64FV")
      (footprint "eagle-import:WSON-8-5X6")
      (libsource (lib "eagle-import") (part "W25Q64FV"))
    )
    (comp (ref "U$5")
      (value "NUF2042XV6")
      (footprint "eagle-import:SOT563-6")
      (libsource (lib "eagle-import") (part "NUF2042XV6"))
    )
    (comp (ref "J802")
      (value "DF13C-3P-1.25V")
      (footprint "eagle-import:DF13C-3P-1.25V")
      (fields (field (name "PARTNO") "DF13C-3P-1.25V(20)"))
      (libsource (lib "eagle-import") (part "DF13-3P-1.25V"))
    )
    (comp (ref "LED701")
      (value "AMBER")
      (footprint "eagle-import:0603-LED")
      (fields (field (name "PARTNO") "APTD1608SECK"))
      (libsource (lib "eagle-import") (part "LED0603"))
    )
    (comp (ref "LED704")
      (value "GREEN")
      (footprint "eagle-import:0603-LED")
      (fields (field (name "PARTNO") "APTD1608CGCK"))
      (libsource (lib "eagle-import") (part "LED0603"))
    )
    (comp (ref "R3")
      (value "220R")
      (footprint "eagle-import:0402-RES")
      (fields (field (name "PARTNO") "RC0402FR-07220RL"))
      (libsource (lib "eagle-import") (part "RESISTOR0402-RES"))
    )
    (comp (ref "R707")
      (value "220R")
      (footprint "eagle-import:0402-RES")
      (fields (field (name "PARTNO") "RC0402FR-07220RL"))
      (libsource (lib "eagle-import") (part "RESISTOR0402-RES"))
    )
    (comp (ref "R710")
      (value "47R")
      (footprint "eagle-import:0402-RES")
      (fields (field (name "PARTNO") "RC0402JR-0747RL"))
      (libsource (lib "eagle-import") (part "RESISTOR0402-RES"))
    )
    (comp (ref "R711")
      (value "220R")
      (footprint "eagle-import:0402-RES")
      (fields (field (name "PARTNO") "RC0402FR-07220RL"))
      (libsource (lib "eagle-import") (part "RESISTOR0402-RES"))
    )
    (comp (ref "R713")
      (value "1K5")
      (footprint "eagle-import:0402-RES")
      (fields (field (name "PARTNO") "RC0402FR-071K5L"))
      (libsource (lib "eagle-import") (part "RESISTOR0402-RES"))
    )
    (comp (ref "U$701")
      (value "PESD0402-140")
      (footprint "eagle-import:0402-TVS")
      (libsource (lib "eagle-import") (part "DIODE-TVS"))
    )
    (comp (ref "C102")
      (value "8p")
      (footprint "eagle-import:0402-CAP")
      (fields (field (name "PARTNO") "C1005C0G1H080C"))
      (libsource (lib "eagle-import") (part "CAP0402"))
    )
    (comp (ref "C103")
      (value "8p")
      (footprint "eagle-import:0402-CAP")
      (fields (field (name "PARTNO") "C1005C0G1H080C"))
      (libsource (lib "eagle-import") (part "CAP0402"))
    )
    (comp (ref "R102")
      (value "10K")
      (footprint "eagle-import:0402-RES")
      (fields (field (name "PARTNO") "RC0402FR-0710KL"))
      (libsource (lib "eagle-import") (part "RESISTOR0402-RES"))
    )
    (comp (ref "X101")
      (value "3.2x2.5 mm / 24 MHz / 15 ppm")
      (footprint "eagle-import:OSCILLATOR-3.2X2.5")
      (fields (field (name "PARTNO") "NX3225SA-24.000000MHZ"))
      (libsource (lib "eagle-import") (part "OSCILLATOR-3.2X2.5"))
    )
  )
  (nets
    (net (code "1") (name "ACCEL_DRDY") (class "Default")
      (node (ref "U$2") (pin "11") (pinfunction "INT1_11") (pintype "bidirectional"))
      (node (ref "U101") (pin "90") (pinfunction "PB4_90") (pintype "bidirectional"))
    )
    (net (code "2") (name "ALARM") (class "Default")
      (node (ref "U101") (pin "77") (pinfunction "PA15_77") (pintype "bidirectional"))
    )
    (net (code "3") (name "CAN1_H") (class "Default")
      (node (ref "J405") (pin "P$2") (pinfunction "2_P$2") (pintype "passive"))
      (node (ref "R409") (pin "P$1") (pinfunction "1_P$1") (pintype "passive"))
      (node (ref "U401") (pin "7") (pinfunction "CANH_7") (pintype "bidirectional"))
    )
    (net (code "4") (name "CAN1_L") (class "Default")
      (node (ref "J405") (pin "P$3") (pinfunction "3_P$3") (pintype "passive"))
      (node (ref "SJ1") (pin "2") (pinfunction "2_2") (pintype "passive"))
      (node (ref "U401") (pin "6") (pinfunction "CANL_6") (pintype "bidirectional"))
    )
    (net (code "5") (name "CAN1_RX") (class "Default")
      (node (ref "U101") (pin "81") (pinfunction "PD0_81") (pintype "bidirectional"))
      (node (ref "U401") (pin "4") (pinfunction "DOUT_4") (pintype "output"))
    )
    (net (code "6") (name "CAN1_TX") (class "Default")
      (node (ref "U101") (pin "82") (pinfunction "PD1_82") (pintype "bidirectional"))
      (node (ref "U401") (pin "1") (pinfunction "DIN_1") (pintype "input"))
    )
    (net (code "7") (name "CAN2_RX") (class "Default")
      (node (ref "U101") (pin "51") (pinfunction "PB12_51") (pintype "bidirectional"))
      (node (ref "U2") (pin "4") (pinfunction "DOUT_4") (pintype "output"))
    )
    (net (code "8") (name "CAN2_TX") (class "Default")
      (node (ref "U101") (pin "92") (pinfunction "PB6_92") (pintype "bidirectional"))
      (node (ref "U2") (pin "1") (pinfunction "DIN_1") (pintype "input"))
    )
    (net (code "9") (name "FMU-BOOT0") (class "Default")
      (node (ref "FMU-BOOT0") (pin "P$1") (pinfunction "P$1_P$1") (pintype "passive"))
      (node (ref "R611") (pin "P$2") (pinfunction "2_P$2") (pintype "passive"))
      (node (ref "U101") (pin "94") (pinfunction "BOOT0_94") (pintype "input"))
    )
    (net (code "10") (name "FMU-CH1") (class "Default")
      (node (ref "L1") (pin "P$1") (pinfunction "P$1_P$1") (pintype "bidirectional"))
      (node (ref "U101") (pin "45") (pinfunction "PE14_45") (pintype "bidirectional"))
    )
    (net (code "11") (name "FMU-CH2") (class "Default")
      (node (ref "L1") (pin "P$2") (pinfunction "P$1_P$2") (pintype "bidirectional"))
      (node (ref "U101") (pin "44") (pinfunction "PE13_44") (pintype "bidirectional"))
    )
    (net (code "12") (name "FMU-CH3") (class "Default")
      (node (ref "L1") (pin "P$3") (pinfunction "P$1_P$3") (pintype "bidirectional"))
      (node (ref "U101") (pin "42") (pinfunction "PE11_42") (pintype "bidirectional"))
    )
    (net (code "13") (name "FMU-CH4") (class "Default")
      (node (ref "L1") (pin "P$4") (pinfunction "P$1_P$4") (pintype "bidirectional"))
      (node (ref "U101") (pin "40") (pinfunction "PE9_40") (pintype "bidirectional"))
    )
    (net (code "14") (name "FMU-CH5") (class "Default")
      (node (ref "L1") (pin "P$5") (pinfunction "P$1_P$5") (pintype "bidirectional"))
      (node (ref "U101") (pin "60") (pinfunction "PD13_60") (pintype "bidirectional"))
    )
    (net (code "15") (name "FMU-CH6") (class "Default")
      (node (ref "L1") (pin "P$6") (pinfunction "P$1_P$6") (pintype "bidirectional"))
      (node (ref "U101") (pin "62") (pinfunction "PD15_62") (pintype "bidirectional"))
    )
    (net (code "16") (name "FMU-CH7") (class "Default")
      (node (ref "L1") (pin "P$7") (pinfunction "P$1_P$7") (pintype "bidirectional"))
      (node (ref "U101") (pin "24") (pinfunction "PA1_24") (pintype "bidirectional"))
    )
    (net (code "17") (name "FMU-CH8") (class "Default")
      (node (ref "L1") (pin "P$8") (pinfunction "P$1_P$8") (pintype "bidirectional"))
      (node (ref "U101") (pin "61") (pinfunction "PD14_61") (pintype "bidirectional"))
    )
    (net (code "18") (name "FMU-CH9") (class "Default")
      (node (ref "U101") (pin "25") (pinfunction "PA2_25") (pintype "bidirectional"))
    )
    (net (code "19") (name "FMU-CH10") (class "Default")
      (node (ref "U101") (pin "26") (pinfunction "PA3_26") (pintype "bidirectional"))
    )
    (net (code "20") (name "FMU-I2C1_SCL") (class "Default")
      (node (ref "L6") (pin "P$8") (pinfunction "P$1_P$8") (pintype "bidirectional"))
      (node (ref "R401") (pin "P$1") (pinfunction "1_P$1") (pintype "passive"))
      (node (ref "U101") (pin "95") (pinfunction "PB8_95") (pintype "bidirectional"))
    )
    (net (code "21") (name "FMU-I2C1_SDA") (class "Default")
      (node (ref "L6") (pin "P$7") (pinfunction "P$1_P$7") (pintype "bidirectional"))
      (node (ref "R402") (pin "P$1") (pinfunction "1_P$1") (pintype "passive"))
      (node (ref "U101") (pin "96") (pinfunction "PB9_96") (pintype "bidirectional"))
    )
    (net (code "22") (name "FMU-I2C2_SCL") (class "Default")
      (node (ref "L6") (pin "P$2") (pinfunction "P$1_P$2") (pintype "bidirectional"))
      (node (ref "R1") (pin "P$1") (pinfunction "1_P$1") (pintype "passive"))
      (node (ref "U101") (pin "47") (pinfunction "PB10_47") (pintype "bidirectional"))
    )
    (net (code "23") (name "FMU-I2C2_SDA") (class "Default")
      (node (ref "L6") (pin "P$1") (pinfunction "P$1_P$1") (pintype "bidirectional"))
      (node (ref "R2") (pin "P$1") (pinfunction "1_P$1") (pintype "passive"))
      (node (ref "U101") (pin "48") (pinfunction "PB11_48") (pintype "bidirectional"))
    )
    (net (code "24") (name "FMU-LED_SAFETY") (class "Default")
      (node (ref "R710") (pin "P$2") (pinfunction "2_P$2") (pintype "passive"))
    )
    (net (code "25") (name "FMU-SWCLK") (class "Default")
      (node (ref "JX301") (pin "4") (pinfunction "S_4") (pintype "passive"))
      (node (ref "U101") (pin "76") (pinfunction "PA14_76") (pintype "bidirectional"))
    )
    (net (code "26") (name "FMU-SWDIO") (class "Default")
      (node (ref "JX301") (pin "2") (pinfunction "S_2") (pintype "passive"))
      (node (ref "U101") (pin "72") (pinfunction "PA13_72") (pintype "bidirectional"))
    )
    (net (code "27") (name "FMU-SWO") (class "Default")
      (node (ref "JX301") (pin "6") (pinfunction "S_6") (pintype "passive"))
      (node (ref "U101") (pin "89") (pinfunction "PB3_89") (pintype "bidirectional"))
    )
    (net (code "28") (name "FMU-UART7_RX") (class "Default")
      (node (ref "L3") (pin "P$5") (pinfunction "P$1_P$5") (pintype "bidirectional"))
      (node (ref "U101") (pin "38") (pinfunction "PE7_38") (pintype "bidirectional"))
    )
    (net (code "29") (name "FMU-UART7_TX") (class "Default")
      (node (ref "L3") (pin "P$6") (pinfunction "P$1_P$6") (pintype "bidirectional"))
      (node (ref "U101") (pin "39") (pinfunction "PE8_39") (pintype "bidirectional"))
    )
    (net (code "30") (name "FMU-UART8_RX") (class "Default")
      (node (ref "U101") (pin "97") (pinfunction "PE0_97") (pintype "bidirectional"))
    )
    (net (code "31") (name "FMU-UART8_TX") (class "Default")
      (node (ref "U101") (pin "98") (pinfunction "PE1_98") (pintype "bidirectional"))
    )
    (net (code "32") (name "FMU-USART2_CTS") (class "Default")
      (node (ref "L2") (pin "P$8") (pinfunction "P$1_P$8") (pintype "bidirectional"))
      (node (ref "U101") (pin "84") (pinfunction "PD3_84") (pintype "bidirectional"))
    )
    (net (code "33") (name "FMU-USART2_RTS") (class "Default")
      (node (ref "L2") (pin "P$7") (pinfunction "P$1_P$7") (pintype "bidirectional"))
      (node (ref "U101") (pin "85") (pinfunction "PD4_85") (pintype "bidirectional"))
    )
    (net (code "34") (name "FMU-USART2_RX") (class "Default")
      (node (ref "L2") (pin "P$5") (pinfunction "P$1_P$5") (pintype "bidirectional"))
      (node (ref "U101") (pin "87") (pinfunction "PD6_87") (pintype "bidirectional"))
    )
    (net (code "35") (name "FMU-USART2_TX") (class "Default")
      (node (ref "L2") (pin "P$6") (pinfunction "P$1_P$6") (pintype "bidirectional"))
      (node (ref "U101") (pin "86") (pinfunction "PD5_86") (pintype "bidirectional"))
    )
    (net (code "36") (name "FMU-USART3_CTS") (class "Default")
      (node (ref "L2") (pin "P$2") (pinfunction "P$1_P$2") (pintype "bidirectional"))
      (node (ref "U101") (pin "58") (pinfunction "PD11_58") (pintype "bidirectional"))
    )
    (net (code "37") (name "FMU-USART3_RTS") (class "Default")
      (node (ref "L2") (pin "P$1") (pinfunction "P$1_P$1") (pintype "bidirectional"))
      (node (ref "U101") (pin "59") (pinfunction "PD12_59") (pintype "bidirectional"))
    )
    (net (code "38") (name "FMU-USART3_RX") (class "Default")
      (node (ref "L2") (pin "P$3") (pinfunction "P$1_P$3") (pintype "bidirectional"))
      (node (ref "U101") (pin "56") (pinfunction "PD9_56") (pintype "bidirectional"))
    )
    (net (code "39") (name "FMU-USART3_TX") (class "Default")
      (node (ref "L2") (pin "P$4") (pinfunction "P$1_P$4") (pintype "bidirectional"))
      (node (ref "U101") (pin "55") (pinfunction "PD8_55") (pintype "bidirectional"))
    )
    (net (code "40") (name "FMU-VDD_3V3") (class "Default")
      (node (ref "C13") (pin "P$1") (pinfunction "1_P$1") (pintype "passive"))
      (node (ref "C14") (pin "P$1") (pinfunction "1_P$1") (pintype "passive"))
      (node (ref "C15") (pin "P$1") (pinfunction "1_P$1") (pintype "passive"))
      (node (ref "C4") (pin "P$1") (pinfunction "1_P$1") (pintype "passive"))
      (node (ref "C402") (pin "P$1") (pinfunction "1_P$1") (pintype "passive"))
      (node (ref "C603") (pin "P$1") (pinfunction "1_P$1") (pintype "passive"))
      (node (ref "C604") (pin "P$1") (pinfunction "1_P$1") (pintype "passive"))
      (node (ref "C606") (pin "P$1") (pinfunction "1_P$1") (pintype "passive"))
      (node (ref "C607") (pin "P$1") (pinfunction "1_P$1") (pintype "passive"))
      (node (ref "C608") (pin "P$1") (pinfunction "1_P$1") (pintype "passive"))
      (node (ref "C610") (pin "P$1") (pinfunction "1_P$1") (pintype "passive"))
      (node (ref "C612") (pin "P$1") (pinfunction "1_P$1") (pintype "passive"))
      (node (ref "J802") (pin "P$1") (pinfunction "1_P$1") (pintype "passive"))
      (node (ref "JX301") (pin "1") (pinfunction "S_1") (pintype "passive"))
      (node (ref "R1") (pin "P$2") (pinfunction "2_P$2") (pintype "passive"))
      (node (ref "R2") (pin "P$2") (pinfunction "2_P$2") (pintype "passive"))
      (node (ref "R401") (pin "P$2") (pinfunction "2_P$2") (pintype "passive"))
      (node (ref "R402") (pin "P$2") (pinfunction "2_P$2") (pintype "passive"))
      (node (ref "R608") (pin "P$2") (pinfunction "2_P$2") (pintype "passive"))
      (node (ref "U$3") (pin "8") (pinfunction "VCC_8") (pintype "bidirectional"))
      (node (ref "U$605") (pin "7") (pinfunction "VOUT2_7") (pintype "bidirectional"))
      (node (ref "U$701") (pin "C") (pinfunction "C_C") (pintype "passive"))
      (node (ref "U101") (pin "100") (pinfunction "VDD_100") (pintype "power_in"))
      (node (ref "U101") (pin "11") (pinfunction "VDD_11") (pintype "power_in"))
      (node (ref "U101") (pin "19") (pinfunction "VDD_19") (pintype "power_in"))
      (node (ref "U101") (pin "21") (pinfunction "VREF+_21") (pintype "input"))
      (node (ref "U101") (pin "22") (pinfunction "VDDA_22") (pintype "power_in"))
      (node (ref "U101") (pin "28") (pinfunction "VDD_28") (pintype "power_in"))
      (node (ref "U101") (pin "50") (pinfunction "VDD_50") (pintype "power_in"))
      (node (ref "U101") (pin "75") (pinfunction "VDD_75") (pintype "power_in"))
      (node (ref "U2") (pin "3") (pinfunction "VCC_3") (pintype "input"))
      (node (ref "U401") (pin "3") (pinfunction "VCC_3") (pintype "input"))
    )
    (net (code "41") (name "FMU-~{RESET}") (class "Default")
      (node (ref "C609") (pin "P$2") (pinfunction "2_P$2") (pintype "passive"))
      (node (ref "S601") (pin "A1") (pinfunction "1_A1") (pintype "passive"))
      (node (ref "U$605") (pin "3") (pinfunction "POR2_3") (pintype "bidirectional"))
      (node (ref "U101") (pin "14") (pinfunction "NRST_14") (pintype "input"))
    )
    (net (code "42") (name "FMU_AUX_ADC1") (class "Default")
      (node (ref "R408") (pin "P$1") (pinfunction "1_P$1") (pintype "passive"))
      (node (ref "U101") (pin "18") (pinfunction "PC3_18") (pintype "bidirectional"))
    )
    (net (code "43") (name "FMU_AUX_ADC2") (class "Default")
      (node (ref "R407") (pin "P$1") (pinfunction "1_P$1") (pintype "passive"))
      (node (ref "U101") (pin "33") (pinfunction "PC4_33") (pintype "bidirectional"))
    )
    (net (code "44") (name "FRAM_MISO") (class "Default")
      (node (ref "U101") (pin "53") (pinfunction "PB14_53") (pintype "bidirectional"))
    )
    (net (code "45") (name "FRAM_MOSI") (class "Default")
      (node (ref "U101") (pin "54") (pinfunction "PB15_54") (pintype "bidirectional"))
    )
    (net (code "46") (name "FRAM_SCK") (class "Default")
      (node (ref "U101") (pin "52") (pinfunction "PB13_52") (pintype "bidirectional"))
    )
    (net (code "47") (name "GND") (class "Default")
      (node (ref "C1") (pin "2") (pinfunction "2_2") (pintype "passive"))
      (node (ref "C10") (pin "2") (pinfunction "2_2") (pintype "passive"))
      (node (ref "C1001") (pin "P$2") (pinfunction "2_P$2") (pintype "passive"))
      (node (ref "C1002") (pin "P$2") (pinfunction "2_P$2") (pintype "passive"))
      (node (ref "C1003") (pin "P$2") (pinfunction "2_P$2") (pintype "passive"))
      (node (ref "C1004") (pin "P$2") (pinfunction "2_P$2") (pintype "passive"))
      (node (ref "C102") (pin "P$2") (pinfunction "2_P$2") (pintype "passive"))
      (node (ref "C103") (pin "P$1") (pinfunction "1_P$1") (pintype "passive"))
      (node (ref "C12") (pin "P$2") (pinfunction "2_P$2") (pintype "passive"))
      (node (ref "C13") (pin "P$2") (pinfunction "2_P$2") (pintype "passive"))
      (node (ref "C14") (pin "P$2") (pinfunction "2_P$2") (pintype "passive"))
      (node (ref "C15") (pin "P$2") (pinfunction "2_P$2") (pintype "passive"))
      (node (ref "C2") (pin "P$2") (pinfunction "2_P$2") (pintype "passive"))
      (node (ref "C3") (pin "P$2") (pinfunction "2_P$2") (pintype "passive"))
      (node (ref "C4") (pin "P$2") (pinfunction "2_P$2") (pintype "passive"))
      (node (ref "C402") (pin "P$2") (pinfunction "2_P$2") (pintype "passive"))
      (node (ref "C5") (pin "P$2") (pinfunction "2_P$2") (pintype "passive"))
      (node (ref "C505") (pin "P$2") (pinfunction "2_P$2") (pintype "passive"))
      (node (ref "C506") (pin "P$2") (pinfunction "2_P$2") (pintype "passive"))
      (node (ref "C6") (pin "P$2") (pinfunction "2_P$2") (pintype "passive"))
      (node (ref "C601") (pin "P$2") (pinfunction "2_P$2") (pintype "passive"))
      (node (ref "C602") (pin "P$1") (pinfunction "1_P$1") (pintype "passive"))
      (node (ref "C603") (pin "P$2") (pinfunction "2_P$2") (pintype "passive"))
      (node (ref "C604") (pin "P$2") (pinfunction "2_P$2") (pintype "passive"))
      (node (ref "C605") (pin "P$2") (pinfunction "2_P$2") (pintype "passive"))
      (node (ref "C606") (pin "P$2") (pinfunction "2_P$2") (pintype "passive"))
      (node (ref "C607") (pin "P$2") (pinfunction "2_P$2") (pintype "passive"))
      (node (ref "C608") (pin "P$2") (pinfunction "2_P$2") (pintype "passive"))
      (node (ref "C609") (pin "P$1") (pinfunction "1_P$1") (pintype "passive"))
      (node (ref "C610") (pin "P$2") (pinfunction "2_P$2") (pintype "passive"))
      (node (ref "C611") (pin "P$2") (pinfunction "2_P$2") (pintype "passive"))
      (node (ref "C612") (pin "P$2") (pinfunction "2_P$2") (pintype "passive"))
      (node (ref "C613") (pin "P$2") (pinfunction "2_P$2") (pintype "passive"))
      (node (ref "C7") (pin "P$2") (pinfunction "2_P$2") (pintype "passive"))
      (node (ref "C8") (pin "2") (pinfunction "2_2") (pintype "passive"))
      (node (ref "C9") (pin "2") (pinfunction "2_2") (pintype "passive"))
      (node (ref "D3") (pin "2") (pinfunction "A_2") (pintype "passive"))
      (node (ref "J1") (pin "GND_S1") (pinfunction "S_GND_S1") (pintype "passive"))
      (node (ref "J1") (pin "GND_S2") (pinfunction "S_GND_S2") (pintype "passive"))
      (node (ref "J1") (pin "GND_S3") (pinfunction "S_GND_S3") (pintype "passive"))
      (node (ref "J1") (pin "GND_S4") (pinfunction "S_GND_S4") (pintype "passive"))
      (node (ref "J1") (pin "GND_S5") (pinfunction "S_GND_S5") (pintype "passive"))
      (node (ref "J1") (pin "GND_S6") (pinfunction "S_GND_S6") (pintype "passive"))
      (node (ref "J1") (pin "GND_S7") (pinfunction "S_GND_S7") (pintype "passive"))
      (node (ref "J1") (pin "GND_S8") (pinfunction "S_GND_S8") (pintype "passive"))
      (node (ref "J2") (pin "P$4") (pinfunction "4_P$4") (pintype "passive"))
      (node (ref "J201") (pin "P$6") (pinfunction "6_P$6") (pintype "passive"))
      (node (ref "J202") (pin "P$6") (pinfunction "6_P$6") (pintype "passive"))
      (node (ref "J203") (pin "P$6") (pinfunction "6_P$6") (pintype "passive"))
      (node (ref "J3") (pin "P$4") (pinfunction "4_P$4") (pintype "passive"))
      (node (ref "J302") (pin "P$4") (pinfunction "4_P$4") (pintype "passive"))
      (node (ref "J401") (pin "P$4") (pinfunction "4_P$4") (pintype "passive"))
      (node (ref "J403") (pin "P$7") (pinfunction "7_P$7") (pintype "passive"))
      (node (ref "J405") (pin "P$4") (pinfunction "4_P$4") (pintype "passive"))
      (node (ref "JP5") (pin "2") (pinfunction "2_2") (pintype "passive"))
      (node (ref "JX301") (pin "3") (pinfunction "S_3") (pintype "passive"))
      (node (ref "JX301") (pin "5") (pinfunction "S_5") (pintype "passive"))
      (node (ref "JX301") (pin "9") (pinfunction "S_9") (pintype "passive"))
      (node (ref "L1") (pin "P$EP") (pinfunction "GND_P$EP") (pintype "power_in"))
      (node (ref "L2") (pin "P$EP") (pinfunction "GND_P$EP") (pintype "power_in"))
      (node (ref "L201") (pin "P$3") (pinfunction "P$3_P$3") (pintype "bidirectional"))
      (node (ref "L201") (pin "P$4") (pinfunction "P$3_P$4") (pintype "bidirectional"))
      (node (ref "L201") (pin "P$5") (pinfunction "P$3_P$5") (pintype "bidirectional"))
      (node (ref "L202") (pin "P$3") (pinfunction "P$3_P$3") (pintype "bidirectional"))
      (node (ref "L202") (pin "P$4") (pinfunction "P$3_P$4") (pintype "bidirectional"))
      (node (ref "L202") (pin "P$5") (pinfunction "P$3_P$5") (pintype "bidirectional"))
      (node (ref "L203") (pin "P$3") (pinfunction "P$3_P$3") (pintype "bidirectional"))
      (node (ref "L203") (pin "P$4") (pinfunction "P$3_P$4") (pintype "bidirectional"))
      (node (ref "L203") (pin "P$5") (pinfunction "P$3_P$5") (pintype "bidirectional"))
      (node (ref "L3") (pin "P$EP") (pinfunction "GND_P$EP") (pintype "power_in"))
      (node (ref "L4") (pin "P$3") (pinfunction "P$3_P$3") (pintype "bidirectional"))
      (node (ref "L4") (pin "P$4") (pinfunction "P$3_P$4") (pintype "bidirectional"))
      (node (ref "L4") (pin "P$5") (pinfunction "P$3_P$5") (pintype "bidirectional"))
      (node (ref "L402") (pin "P$3") (pinfunction "P$3_P$3") (pintype "bidirectional"))
      (node (ref "L402") (pin "P$4") (pinfunction "P$3_P$4") (pintype "bidirectional"))
      (node (ref "L402") (pin "P$5") (pinfunction "P$3_P$5") (pintype "bidirectional"))
      (node (ref "L403") (pin "P$3") (pinfunction "P$3_P$3") (pintype "bidirectional"))
      (node (ref "L403") (pin "P$4") (pinfunction "P$3_P$4") (pintype "bidirectional"))
      (node (ref "L403") (pin "P$5") (pinfunction "P$3_P$5") (pintype "bidirectional"))
      (node (ref "L5") (pin "P$3") (pinfunction "P$3_P$3") (pintype "bidirectional"))
      (node (ref "L5") (pin "P$4") (pinfunction "P$3_P$4") (pintype "bidirectional"))
      (node (ref "L5") (pin "P$5") (pinfunction "P$3_P$5") (pintype "bidirectional"))
      (node (ref "L6") (pin "P$EP") (pinfunction "GND_P$EP") (pintype "power_in"))
      (node (ref "L7") (pin "P$3") (pinfunction "P$3_P$3") (pintype "bidirectional"))
      (node (ref "L7") (pin "P$4") (pinfunction "P$3_P$4") (pintype "bidirectional"))
      (node (ref "L7") (pin "P$5") (pinfunction "P$3_P$5") (pintype "bidirectional"))
      (node (ref "R1002") (pin "P$1") (pinfunction "1_P$1") (pintype "passive"))
      (node (ref "R102") (pin "P$2") (pinfunction "2_P$2") (pintype "passive"))
      (node (ref "R5") (pin "P$1") (pinfunction "1_P$1") (pintype "passive"))
      (node (ref "R603") (pin "P$1") (pinfunction "1_P$1") (pintype "passive"))
      (node (ref "R606") (pin "P$2") (pinfunction "2_P$2") (pintype "passive"))
      (node (ref "R610") (pin "P$2") (pinfunction "2_P$2") (pintype "passive"))
      (node (ref "R611") (pin "P$1") (pinfunction "1_P$1") (pintype "passive"))
      (node (ref "R711") (pin "P$1") (pinfunction "1_P$1") (pintype "passive"))
      (node (ref "R713") (pin "P$2") (pinfunction "2_P$2") (pintype "passive"))
      (node (ref "R919") (pin "P$1") (pinfunction "1_P$1") (pintype "passive"))
      (node (ref "S601") (pin "B3") (pinfunction "2_B3") (pintype "passive"))
      (node (ref "U$1") (pin "3") (pinfunction "3_3") (pintype "bidirectional"))
      (node (ref "U$1002") (pin "2") (pinfunction "GND_2") (pintype "bidirectional"))
      (node (ref "U$1002") (pin "GND") (pinfunction "GND_GND") (pintype "bidirectional"))
      (node (ref "U$14") (pin "3") (pinfunction "3_3") (pintype "bidirectional"))
      (node (ref "U$15") (pin "11") (pinfunction "GND_11") (pintype "power_in"))
      (node (ref "U$15") (pin "15") (pinfunction "PGND_15") (pintype "power_in"))
      (node (ref "U$15") (pin "16") (pinfunction "PGND_16") (pintype "power_in"))
      (node (ref "U$15") (pin "17") (pinfunction "PGND_17") (pintype "power_in"))
      (node (ref "U$15") (pin "18") (pinfunction "PGND_18") (pintype "power_in"))
      (node (ref "U$15") (pin "19") (pinfunction "PGND_19") (pintype "power_in"))
      (node (ref "U$15") (pin "20") (pinfunction "PGND_20") (pintype "power_in"))
      (node (ref "U$15") (pin "21") (pinfunction "PGND_21") (pintype "power_in"))
      (node (ref "U$15") (pin "22") (pinfunction "PGND_22") (pintype "power_in"))
      (node (ref "U$15") (pin "23") (pinfunction "PGND_23") (pintype "power_in"))
      (node (ref "U$15") (pin "4") (pinfunction "PS/SYNC_4") (pintype "input"))
      (node (ref "U$15") (pin "6") (pinfunction "PGND_6") (pintype "power_in"))
      (node (ref "U$15") (pin "7") (pinfunction "PGND_7") (pintype "power_in"))
      (node (ref "U$15") (pin "8") (pinfunction "PGND_8") (pintype "power_in"))
      (node (ref "U$15") (pin "9") (pinfunction "PGND_9") (pintype "power_in"))
      (node (ref "U$15") (pin "EP") (pinfunction "PGND_EP") (pintype "power_in"))
      (node (ref "U$2") (pin "10") (pinfunction "RSV1_10") (pintype "input"))
      (node (ref "U$2") (pin "5") (pinfunction "GND_5") (pintype "power_in"))
      (node (ref "U$201") (pin "A") (pinfunction "A_A") (pintype "passive"))
      (node (ref "U$202") (pin "A") (pinfunction "A_A") (pintype "passive"))
      (node (ref "U$203") (pin "A") (pinfunction "A_A") (pintype "passive"))
      (node (ref "U$3") (pin "4") (pinfunction "GND_4") (pintype "bidirectional"))
      (node (ref "U$4") (pin "A") (pinfunction "A_A") (pintype "passive"))
      (node (ref "U$401") (pin "A") (pinfunction "A_A") (pintype "passive"))
      (node (ref "U$404") (pin "A") (pinfunction "A_A") (pintype "passive"))
      (node (ref "U$5") (pin "2") (pinfunction "GND_2") (pintype "bidirectional"))
      (node (ref "U$604") (pin "2") (pinfunction "VSS_2") (pintype "bidirectional"))
      (node (ref "U$604") (pin "6") (pinfunction "VBAT_6") (pintype "bidirectional"))
      (node (ref "U$604") (pin "GND") (pinfunction "VSS_GND") (pintype "bidirectional"))
      (node (ref "U$604") (pin "P$2") (pinfunction "VSS_P$2") (pintype "bidirectional"))
      (node (ref "U$604") (pin "P$3") (pinfunction "VSS_P$3") (pintype "bidirectional"))
      (node (ref "U$605") (pin "2") (pinfunction "GND_2") (pintype "bidirectional"))
      (node (ref "U$605") (pin "GND") (pinfunction "GND_GND") (pintype "bidirectional"))
      (node (ref "U$7") (pin "A") (pinfunction "A_A") (pintype "passive"))
      (node (ref "U$701") (pin "A") (pinfunction "A_A") (pintype "passive"))
      (node (ref "U101") (pin "10") (pinfunction "VSS_10") (pintype "power_in"))
      (node (ref "U101") (pin "20") (pinfunction "VSSA_20") (pintype "power_in"))
      (node (ref "U101") (pin "27") (pinfunction "VSS_27") (pintype "power_in"))
      (node (ref "U101") (pin "74") (pinfunction "VSS_74") (pintype "power_in"))
      (node (ref "U101") (pin "99") (pinfunction "VSS_99") (pintype "power_in"))
      (node (ref "U2") (pin "2") (pinfunction "GND_2") (pintype "power_in"))
      (node (ref "U2") (pin "5") (pinfunction "SHDN_5") (pintype "input"))
      (node (ref "U2") (pin "8") (pinfunction "RS_8") (pintype "input"))
      (node (ref "U401") (pin "2") (pinfunction "GND_2") (pintype "power_in"))
      (node (ref "U401") (pin "5") (pinfunction "SHDN_5") (pintype "input"))
      (node (ref "U401") (pin "8") (pinfunction "RS_8") (pintype "input"))
      (node (ref "X101") (pin "2") (pinfunction "NC_2_2") (pintype "power_in"))
      (node (ref "X101") (pin "4") (pinfunction "NC_4_4") (pintype "power_in"))
    )
    (net (code "48") (name "GPIO_EXT_1") (class "Default")
      (node (ref "J403") (pin "P$6") (pinfunction "6_P$6") (pintype "passive"))
      (node (ref "U101") (pin "8") (pinfunction "PC14_8") (pintype "bidirectional"))
    )
    (net (code "49") (name "GYRO_DRDY") (class "Default")
      (node (ref "U$2") (pin "9") (pinfunction "INT2_9") (pintype "bidirectional"))
      (node (ref "U101") (pin "35") (pinfunction "PB0_35") (pintype "bidirectional"))
    )
    (net (code "50") (name "IO-~{RESET}") (class "Default")
      (node (ref "U$1002") (pin "3") (pinfunction "POR2_3") (pintype "bidirectional"))
    )
    (net (code "51") (name "MAG_DRDY") (class "Default")
      (node (ref "U101") (pin "36") (pinfunction "PB1_36") (pintype "bidirectional"))
    )
    (net (code "52") (name "Net-(C2-1)") (class "Default")
      (node (ref "C2") (pin "P$1") (pinfunction "1_P$1") (pintype "passive"))
      (node (ref "R408") (pin "P$2") (pinfunction "2_P$2") (pintype "passive"))
      (node (ref "U$1") (pin "2") (pinfunction "2_2") (pintype "bidirectional"))
    )
    (net (code "53") (name "Net-(C3-1)") (class "Default")
      (node (ref "C3") (pin "P$1") (pinfunction "1_P$1") (pintype "passive"))
      (node (ref "R407") (pin "P$2") (pinfunction "2_P$2") (pintype "passive"))
      (node (ref "U$1") (pin "1") (pinfunction "1_1") (pintype "bidirectional"))
    )
    (net (code "54") (name "Net-(C5-1)") (class "Default")
      (node (ref "C5") (pin "P$1") (pinfunction "1_P$1") (pintype "passive"))
      (node (ref "U$2") (pin "13") (pinfunction "REGD_13") (pintype "power_in"))
    )
    (net (code "55") (name "Net-(C6-1)") (class "Default")
      (node (ref "C6") (pin "P$1") (pinfunction "1_P$1") (pintype "passive"))
      (node (ref "U$15") (pin "10") (pinfunction "VAUX_10") (pintype "input"))
    )
    (net (code "56") (name "Net-(C102-1)") (class "Default")
      (node (ref "C102") (pin "P$1") (pinfunction "1_P$1") (pintype "passive"))
      (node (ref "U101") (pin "12") (pinfunction "OSC_IN_12") (pintype "input"))
      (node (ref "X101") (pin "3") (pinfunction "3_3") (pintype "bidirectional"))
    )
    (net (code "57") (name "Net-(C103-2)") (class "Default")
      (node (ref "C103") (pin "P$2") (pinfunction "2_P$2") (pintype "passive"))
      (node (ref "U101") (pin "13") (pinfunction "OSC_OUT_13") (pintype "output"))
      (node (ref "X101") (pin "1") (pinfunction "1_1") (pintype "bidirectional"))
    )
    (net (code "58") (name "Net-(C602-2)") (class "Default")
      (node (ref "C602") (pin "P$2") (pinfunction "2_P$2") (pintype "passive"))
      (node (ref "U$605") (pin "6") (pinfunction "CSET_6") (pintype "bidirectional"))
    )
    (net (code "59") (name "Net-(C611-1)") (class "Default")
      (node (ref "C611") (pin "P$1") (pinfunction "1_P$1") (pintype "passive"))
      (node (ref "U101") (pin "49") (pinfunction "VCAP_1_49") (pintype "power_in"))
    )
    (net (code "60") (name "Net-(C613-1)") (class "Default")
      (node (ref "C613") (pin "P$1") (pinfunction "1_P$1") (pintype "passive"))
      (node (ref "U101") (pin "73") (pinfunction "VCAP_2_73") (pintype "power_in"))
    )
    (net (code "61") (name "Net-(C1002-1)") (class "Default")
      (node (ref "C1002") (pin "P$1") (pinfunction "1_P$1") (pintype "passive"))
      (node (ref "U$1002") (pin "6") (pinfunction "CSET_6") (pintype "bidirectional"))
    )
    (net (code "62") (name "Net-(D3-C)") (class "Default")
      (node (ref "D3") (pin "1") (pinfunction "C_1") (pintype "passive"))
      (node (ref "R918") (pin "P$2") (pinfunction "2_P$2") (pintype "passive"))
      (node (ref "R922") (pin "P$1") (pinfunction "1_P$1") (pintype "passive"))
    )
    (net (code "63") (name "Net-(J1A-S)") (class "Default")
      (node (ref "J1") (pin "S1") (pinfunction "S_S1") (pintype "passive"))
      (node (ref "L1") (pin "P$16") (pinfunction "P$2_P$16") (pintype "bidirectional"))
    )
    (net (code "64") (name "Net-(J1B-S)") (class "Default")
      (node (ref "J1") (pin "S2") (pinfunction "S_S2") (pintype "passive"))
      (node (ref "L1") (pin "P$15") (pinfunction "P$2_P$15") (pintype "bidirectional"))
    )
    (net (code "65") (name "Net-(J1C-S)") (class "Default")
      (node (ref "J1") (pin "S3") (pinfunction "S_S3") (pintype "passive"))
      (node (ref "L1") (pin "P$14") (pinfunction "P$2_P$14") (pintype "bidirectional"))
    )
    (net (code "66") (name "Net-(J1D-S)") (class "Default")
      (node (ref "J1") (pin "S4") (pinfunction "S_S4") (pintype "passive"))
      (node (ref "L1") (pin "P$13") (pinfunction "P$2_P$13") (pintype "bidirectional"))
    )
    (net (code "67") (name "Net-(J1E-S)") (class "Default")
      (node (ref "J1") (pin "S5") (pinfunction "S_S5") (pintype "passive"))
      (node (ref "L1") (pin "P$12") (pinfunction "P$2_P$12") (pintype "bidirectional"))
    )
    (net (code "68") (name "Net-(J1F-S)") (class "Default")
      (node (ref "J1") (pin "S6") (pinfunction "S_S6") (pintype "passive"))
      (node (ref "L1") (pin "P$11") (pinfunction "P$2_P$11") (pintype "bidirectional"))
    )
    (net (code "69") (name "Net-(J1G-S)") (class "Default")
      (node (ref "J1") (pin "S7") (pinfunction "S_S7") (pintype "passive"))
      (node (ref "L1") (pin "P$10") (pinfunction "P$2_P$10") (pintype "bidirectional"))
    )
    (net (code "70") (name "Net-(J1H-S)") (class "Default")
      (node (ref "J1") (pin "S8") (pinfunction "S_S8") (pintype "passive"))
      (node (ref "L1") (pin "P$9") (pinfunction "P$2_P$9") (pintype "bidirectional"))
    )
    (net (code "71") (name "Net-(J2-1)") (class "Default")
      (node (ref "J2") (pin "P$1") (pinfunction "1_P$1") (pintype "passive"))
      (node (ref "L5") (pin "P$2") (pinfunction "P$2_P$2") (pintype "bidirectional"))
      (node (ref "U$4") (pin "C") (pinfunction "C_C") (pintype "passive"))
    )
    (net (code "72") (name "Net-(J2-2)") (class "Default")
      (node (ref "J2") (pin "P$2") (pinfunction "2_P$2") (pintype "passive"))
      (node (ref "L6") (pin "P$15") (pinfunction "P$2_P$15") (pintype "bidirectional"))
    )
    (net (code "73") (name "Net-(J2-3)") (class "Default")
      (node (ref "J2") (pin "P$3") (pinfunction "3_P$3") (pintype "passive"))
      (node (ref "L6") (pin "P$16") (pinfunction "P$2_P$16") (pintype "bidirectional"))
    )
    (net (code "74") (name "Net-(J3-1)") (class "Default")
      (node (ref "J3") (pin "P$1") (pinfunction "1_P$1") (pintype "passive"))
      (node (ref "L7") (pin "P$2") (pinfunction "P$2_P$2") (pintype "bidirectional"))
      (node (ref "U$7") (pin "C") (pinfunction "C_C") (pintype "passive"))
    )
    (net (code "75") (name "Net-(J3-2)") (class "Default")
      (node (ref "J3") (pin "P$2") (pinfunction "2_P$2") (pintype "passive"))
      (node (ref "R4") (pin "P$1") (pinfunction "1_P$1") (pintype "passive"))
      (node (ref "U2") (pin "7") (pinfunction "CANH_7") (pintype "bidirectional"))
    )
    (net (code "76") (name "Net-(J3-3)") (class "Default")
      (node (ref "J3") (pin "P$3") (pinfunction "3_P$3") (pintype "passive"))
      (node (ref "SJ2") (pin "2") (pinfunction "2_2") (pintype "passive"))
      (node (ref "U2") (pin "6") (pinfunction "CANL_6") (pintype "bidirectional"))
    )
    (net (code "77") (name "Net-(J201-1)") (class "Default")
      (node (ref "J201") (pin "P$1") (pinfunction "1_P$1") (pintype "passive"))
      (node (ref "L201") (pin "P$2") (pinfunction "P$2_P$2") (pintype "bidirectional"))
      (node (ref "U$201") (pin "C") (pinfunction "C_C") (pintype "passive"))
    )
    (net (code "78") (name "Net-(J202-1)") (class "Default")
      (node (ref "J202") (pin "P$1") (pinfunction "1_P$1") (pintype "passive"))
      (node (ref "L202") (pin "P$2") (pinfunction "P$2_P$2") (pintype "bidirectional"))
      (node (ref "U$202") (pin "C") (pinfunction "C_C") (pintype "passive"))
    )
    (net (code "79") (name "Net-(J203-1)") (class "Default")
      (node (ref "J203") (pin "P$1") (pinfunction "1_P$1") (pintype "passive"))
      (node (ref "L203") (pin "P$2") (pinfunction "P$2_P$2") (pintype "bidirectional"))
      (node (ref "U$203") (pin "C") (pinfunction "C_C") (pintype "passive"))
    )
    (net (code "80") (name "Net-(J302-2)") (class "Default")
      (node (ref "J302") (pin "P$2") (pinfunction "2_P$2") (pintype "passive"))
      (node (ref "U$5") (pin "1") (pinfunction "D1I_1") (pintype "bidirectional"))
    )
    (net (code "81") (name "Net-(J302-3)") (class "Default")
      (node (ref "J302") (pin "P$3") (pinfunction "3_P$3") (pintype "passive"))
      (node (ref "U$5") (pin "3") (pinfunction "D2I_3") (pintype "bidirectional"))
    )
    (net (code "82") (name "Net-(J401-1)") (class "Default")
      (node (ref "J401") (pin "P$1") (pinfunction "1_P$1") (pintype "passive"))
      (node (ref "L4") (pin "P$2") (pinfunction "P$2_P$2") (pintype "bidirectional"))
      (node (ref "U$401") (pin "C") (pinfunction "C_C") (pintype "passive"))
    )
    (net (code "83") (name "Net-(J401-2)") (class "Default")
      (node (ref "J401") (pin "P$2") (pinfunction "2_P$2") (pintype "passive"))
      (node (ref "L6") (pin "P$9") (pinfunction "P$2_P$9") (pintype "bidirectional"))
    )
    (net (code "84") (name "Net-(J401-3)") (class "Default")
      (node (ref "J401") (pin "P$3") (pinfunction "3_P$3") (pintype "passive"))
      (node (ref "L6") (pin "P$10") (pinfunction "P$2_P$10") (pintype "bidirectional"))
    )
    (net (code "85") (name "Net-(J403-1)") (class "Default")
      (node (ref "J403") (pin "P$1") (pinfunction "1_P$1") (pintype "passive"))
      (node (ref "L402") (pin "P$2") (pinfunction "P$2_P$2") (pintype "bidirectional"))
    )
    (net (code "86") (name "Net-(J405-1)") (class "Default")
      (node (ref "J405") (pin "P$1") (pinfunction "1_P$1") (pintype "passive"))
      (node (ref "L403") (pin "P$2") (pinfunction "P$2_P$2") (pintype "bidirectional"))
      (node (ref "U$404") (pin "C") (pinfunction "C_C") (pintype "passive"))
    )
    (net (code "87") (name "Net-(J802-2)") (class "Default")
      (node (ref "J802") (pin "P$2") (pinfunction "2_P$2") (pintype "passive"))
      (node (ref "R710") (pin "P$1") (pinfunction "1_P$1") (pintype "passive"))
    )
    (net (code "88") (name "Net-(L3C-P$2)") (class "Default")
      (node (ref "L3") (pin "P$13") (pinfunction "P$2_P$13") (pintype "bidirectional"))
      (node (ref "L3") (pin "P$14") (pinfunction "P$2_P$14") (pintype "bidirectional"))
      (node (ref "U$14") (pin "1") (pinfunction "1_1") (pintype "bidirectional"))
    )
    (net (code "89") (name "Net-(R3-1)") (class "Default")
      (node (ref "R3") (pin "P$1") (pinfunction "1_P$1") (pintype "passive"))
      (node (ref "R707") (pin "P$2") (pinfunction "2_P$2") (pintype "passive"))
    )
    (net (code "90") (name "Net-(R3-2)") (class "Default")
      (node (ref "LED701") (pin "C") (pinfunction "C_C") (pintype "passive"))
      (node (ref "R3") (pin "P$2") (pinfunction "2_P$2") (pintype "passive"))
    )
    (net (code "91") (name "Net-(R4-2)") (class "Default")
      (node (ref "R4") (pin "P$2") (pinfunction "2_P$2") (pintype "passive"))
      (node (ref "SJ2") (pin "1") (pinfunction "1_1") (pintype "passive"))
    )
    (net (code "92") (name "Net-(R102-1)") (class "Default")
      (node (ref "R102") (pin "P$1") (pinfunction "1_P$1") (pintype "passive"))
      (node (ref "U101") (pin "37") (pinfunction "PB2_37") (pintype "bidirectional"))
    )
    (net (code "93") (name "Net-(R409-2)") (class "Default")
      (node (ref "R409") (pin "P$2") (pinfunction "2_P$2") (pintype "passive"))
      (node (ref "SJ1") (pin "1") (pinfunction "1_1") (pintype "passive"))
    )
    (net (code "94") (name "Net-(R606-1)") (class "Default")
      (node (ref "R606") (pin "P$1") (pinfunction "1_P$1") (pintype "passive"))
      (node (ref "U$604") (pin "7") (pinfunction "ILIM_7") (pintype "bidirectional"))
    )
    (net (code "95") (name "Net-(R711-2)") (class "Default")
      (node (ref "LED704") (pin "C") (pinfunction "C_C") (pintype "passive"))
      (node (ref "R711") (pin "P$2") (pinfunction "2_P$2") (pintype "passive"))
    )
    (net (code "96") (name "Net-(U$15-L1)") (class "Default")
      (node (ref "U$15") (pin "1") (pinfunction "L1_1") (pintype "bidirectional"))
      (node (ref "U$16") (pin "2") (pinfunction "2_2") (pintype "passive"))
    )
    (net (code "97") (name "Net-(U$15-L2)") (class "Default")
      (node (ref "U$15") (pin "14") (pinfunction "L2_14") (pintype "bidirectional"))
      (node (ref "U$16") (pin "1") (pinfunction "1_1") (pintype "passive"))
    )
    (net (code "98") (name "OTG_FS_DM") (class "Default")
      (node (ref "U$5") (pin "4") (pinfunction "D2O_4") (pintype "bidirectional"))
      (node (ref "U101") (pin "70") (pinfunction "PA11_70") (pintype "bidirectional"))
    )
    (net (code "99") (name "OTG_FS_DP") (class "Default")
      (node (ref "U$5") (pin "6") (pinfunction "D1O_6") (pintype "bidirectional"))
      (node (ref "U101") (pin "71") (pinfunction "PA12_71") (pintype "bidirectional"))
    )
    (net (code "100") (name "PPM_INPUT") (class "Default")
      (node (ref "L3") (pin "P$3") (pinfunction "P$1_P$3") (pintype "bidirectional"))
      (node (ref "U101") (pin "23") (pinfunction "PA0_23") (pintype "bidirectional"))
    )
    (net (code "101") (name "SAFETY") (class "Default")
      (node (ref "J802") (pin "P$3") (pinfunction "3_P$3") (pintype "passive"))
      (node (ref "R713") (pin "P$1") (pinfunction "1_P$1") (pintype "passive"))
    )
    (net (code "102") (name "SDIO_CK") (class "Default")
      (node (ref "U$3") (pin "6") (pinfunction "CLK_6") (pintype "bidirectional"))
      (node (ref "U101") (pin "80") (pinfunction "PC12_80") (pintype "bidirectional"))
    )
    (net (code "103") (name "SDIO_CMD") (class "Default")
      (node (ref "U$3") (pin "1") (pinfunction "~{CS}_1") (pintype "bidirectional"))
      (node (ref "U101") (pin "83") (pinfunction "PD2_83") (pintype "bidirectional"))
    )
    (net (code "104") (name "SDIO_D0") (class "Default")
      (node (ref "U$3") (pin "5") (pinfunction "DI/IO0_5") (pintype "bidirectional"))
      (node (ref "U101") (pin "65") (pinfunction "PC8_65") (pintype "bidirectional"))
    )
    (net (code "105") (name "SDIO_D1") (class "Default")
      (node (ref "U$3") (pin "2") (pinfunction "DO/IO1_2") (pintype "bidirectional"))
      (node (ref "U101") (pin "66") (pinfunction "PC9_66") (pintype "bidirectional"))
    )
    (net (code "106") (name "SDIO_D2") (class "Default")
      (node (ref "U$3") (pin "3") (pinfunction "~{WP}/IO2_3") (pintype "bidirectional"))
      (node (ref "U101") (pin "78") (pinfunction "PC10_78") (pintype "bidirectional"))
    )
    (net (code "107") (name "SDIO_D3") (class "Default")
      (node (ref "U$3") (pin "7") (pinfunction "~{HOLD}/IO3_7") (pintype "bidirectional"))
      (node (ref "U101") (pin "79") (pinfunction "PC11_79") (pintype "bidirectional"))
    )
    (net (code "108") (name "SERIAL1_CTS") (class "Default")
      (node (ref "J201") (pin "P$4") (pinfunction "4_P$4") (pintype "passive"))
      (node (ref "L2") (pin "P$9") (pinfunction "P$2_P$9") (pintype "bidirectional"))
    )
    (net (code "109") (name "SERIAL1_RTS") (class "Default")
      (node (ref "J201") (pin "P$5") (pinfunction "5_P$5") (pintype "passive"))
      (node (ref "L2") (pin "P$10") (pinfunction "P$2_P$10") (pintype "bidirectional"))
    )
    (net (code "110") (name "SERIAL1_RX") (class "Default")
      (node (ref "J201") (pin "P$3") (pinfunction "3_P$3") (pintype "passive"))
      (node (ref "L2") (pin "P$12") (pinfunction "P$2_P$12") (pintype "bidirectional"))
    )
    (net (code "111") (name "SERIAL1_TX") (class "Default")
      (node (ref "J201") (pin "P$2") (pinfunction "2_P$2") (pintype "passive"))
      (node (ref "L2") (pin "P$11") (pinfunction "P$2_P$11") (pintype "bidirectional"))
    )
    (net (code "112") (name "SERIAL2_CTS") (class "Default")
      (node (ref "J202") (pin "P$4") (pinfunction "4_P$4") (pintype "passive"))
      (node (ref "L2") (pin "P$15") (pinfunction "P$2_P$15") (pintype "bidirectional"))
    )
    (net (code "113") (name "SERIAL2_RTS") (class "Default")
      (node (ref "J202") (pin "P$5") (pinfunction "5_P$5") (pintype "passive"))
      (node (ref "L2") (pin "P$16") (pinfunction "P$2_P$16") (pintype "bidirectional"))
    )
    (net (code "114") (name "SERIAL2_RX") (class "Default")
      (node (ref "J202") (pin "P$3") (pinfunction "3_P$3") (pintype "passive"))
      (node (ref "L2") (pin "P$14") (pinfunction "P$2_P$14") (pintype "bidirectional"))
    )
    (net (code "115") (name "SERIAL2_TX") (class "Default")
      (node (ref "J202") (pin "P$2") (pinfunction "2_P$2") (pintype "passive"))
      (node (ref "L2") (pin "P$13") (pinfunction "P$2_P$13") (pintype "bidirectional"))
    )
    (net (code "116") (name "SERIAL3_RX") (class "Default")
      (node (ref "J203") (pin "P$3") (pinfunction "3_P$3") (pintype "passive"))
      (node (ref "L3") (pin "P$12") (pinfunction "P$2_P$12") (pintype "bidirectional"))
    )
    (net (code "117") (name "SERIAL3_TX") (class "Default")
      (node (ref "J203") (pin "P$2") (pinfunction "2_P$2") (pintype "passive"))
      (node (ref "L3") (pin "P$11") (pinfunction "P$2_P$11") (pintype "bidirectional"))
    )
    (net (code "118") (name "SPEKTRUM_RX") (class "Default")
      (node (ref "L3") (pin "P$4") (pinfunction "P$1_P$4") (pintype "bidirectional"))
      (node (ref "U101") (pin "69") (pinfunction "PA10_69") (pintype "bidirectional"))
    )
    (net (code "119") (name "SPI_EXT_MISO") (class "Default")
      (node (ref "J403") (pin "P$3") (pinfunction "3_P$3") (pintype "passive"))
      (node (ref "U101") (pin "4") (pinfunction "PE5_4") (pintype "bidirectional"))
    )
    (net (code "120") (name "SPI_EXT_MOSI") (class "Default")
      (node (ref "J403") (pin "P$4") (pinfunction "4_P$4") (pintype "passive"))
      (node (ref "U101") (pin "5") (pinfunction "PE6_5") (pintype "bidirectional"))
    )
    (net (code "121") (name "SPI_EXT_SCK") (class "Default")
      (node (ref "J403") (pin "P$2") (pinfunction "2_P$2") (pintype "passive"))
      (node (ref "U101") (pin "1") (pinfunction "PE2_1") (pintype "bidirectional"))
    )
    (net (code "122") (name "SPI_INT_MISO") (class "Default")
      (node (ref "U$2") (pin "7") (pinfunction "SA0/MISO_7") (pintype "bidirectional"))
      (node (ref "U101") (pin "31") (pinfunction "PA6_31") (pintype "bidirectional"))
    )
    (net (code "123") (name "SPI_INT_MOSI") (class "Default")
      (node (ref "U$2") (pin "6") (pinfunction "SDA/MOSI_6") (pintype "bidirectional"))
      (node (ref "U101") (pin "32") (pinfunction "PA7_32") (pintype "bidirectional"))
    )
    (net (code "124") (name "SPI_INT_SCK") (class "Default")
      (node (ref "U$2") (pin "4") (pinfunction "SCL/CLK_4") (pintype "bidirectional"))
      (node (ref "U101") (pin "30") (pinfunction "PA5_30") (pintype "bidirectional"))
    )
    (net (code "125") (name "VBAT") (class "Default")
      (node (ref "R608") (pin "P$1") (pinfunction "1_P$1") (pintype "passive"))
      (node (ref "U101") (pin "6") (pinfunction "VBAT_6") (pintype "power_in"))
    )
    (net (code "126") (name "VBUS") (class "Default")
      (node (ref "D1") (pin "ANODE") (pinfunction "A_ANODE") (pintype "passive"))
      (node (ref "J302") (pin "P$1") (pinfunction "1_P$1") (pintype "passive"))
      (node (ref "U$5") (pin "5") (pinfunction "VBUS_5") (pintype "bidirectional"))
      (node (ref "U101") (pin "68") (pinfunction "PA9_68") (pintype "bidirectional"))
    )
    (net (code "127") (name "VDD_3V3_PERIPH") (class "Default")
      (node (ref "C1004") (pin "P$1") (pinfunction "1_P$1") (pintype "passive"))
      (node (ref "U$1002") (pin "7") (pinfunction "VOUT2_7") (pintype "bidirectional"))
    )
    (net (code "128") (name "VDD_3V3_PERIPH_EN") (class "Default")
      (node (ref "R5") (pin "P$2") (pinfunction "2_P$2") (pintype "passive"))
      (node (ref "U$1002") (pin "4") (pinfunction "EN2_4") (pintype "bidirectional"))
    )
    (net (code "129") (name "VDD_3V3_SENSORS") (class "Default")
      (node (ref "C1003") (pin "P$1") (pinfunction "1_P$1") (pintype "passive"))
      (node (ref "C505") (pin "P$1") (pinfunction "1_P$1") (pintype "passive"))
      (node (ref "C506") (pin "P$1") (pinfunction "1_P$1") (pintype "passive"))
      (node (ref "U$1002") (pin "8") (pinfunction "VOUT1_8") (pintype "bidirectional"))
      (node (ref "U$2") (pin "1") (pinfunction "VDD_IO_1") (pintype "power_in"))
      (node (ref "U$2") (pin "14") (pinfunction "VDD_14") (pintype "power_in"))
      (node (ref "U$2") (pin "15") (pinfunction "RSV2_15") (pintype "input"))
    )
    (net (code "130") (name "VDD_3V3_SENSORS_EN") (class "Default")
      (node (ref "R1002") (pin "P$2") (pinfunction "2_P$2") (pintype "passive"))
      (node (ref "U$1002") (pin "5") (pinfunction "EN1_5") (pintype "bidirectional"))
      (node (ref "U101") (pin "2") (pinfunction "PE3_2") (pintype "bidirectional"))
    )
    (net (code "131") (name "VDD_3V3_SPEKTRUM") (class "Default")
      (node (ref "C605") (pin "P$1") (pinfunction "1_P$1") (pintype "passive"))
      (node (ref "U$14") (pin "2") (pinfunction "2_2") (pintype "bidirectional"))
      (node (ref "U$605") (pin "8") (pinfunction "VOUT1_8") (pintype "bidirectional"))
    )
    (net (code "132") (name "VDD_3V3_SPEKTRUM_EN") (class "Default")
      (node (ref "R603") (pin "P$2") (pinfunction "2_P$2") (pintype "passive"))
      (node (ref "U$605") (pin "5") (pinfunction "EN1_5") (pintype "bidirectional"))
    )
    (net (code "133") (name "VDD_5V") (class "Default")
      (node (ref "C10") (pin "1") (pinfunction "1_1") (pintype "passive"))
      (node (ref "C1001") (pin "P$1") (pinfunction "1_P$1") (pintype "passive"))
      (node (ref "C601") (pin "P$1") (pinfunction "1_P$1") (pintype "passive"))
      (node (ref "C7") (pin "P$1") (pinfunction "1_P$1") (pintype "passive"))
      (node (ref "C8") (pin "1") (pinfunction "1_1") (pintype "passive"))
      (node (ref "C9") (pin "1") (pinfunction "1_1") (pintype "passive"))
      (node (ref "LED701") (pin "A") (pinfunction "A_A") (pintype "passive"))
      (node (ref "LED704") (pin "A") (pinfunction "A_A") (pintype "passive"))
      (node (ref "R607") (pin "P$1") (pinfunction "1_P$1") (pintype "passive"))
      (node (ref "R609") (pin "P$2") (pinfunction "2_P$2") (pintype "passive"))
      (node (ref "U$1002") (pin "1") (pinfunction "VIN_1") (pintype "bidirectional"))
      (node (ref "U$15") (pin "13") (pinfunction "VOUT_13") (pintype "power_in"))
      (node (ref "U$604") (pin "1") (pinfunction "IN_1") (pintype "bidirectional"))
      (node (ref "U$605") (pin "1") (pinfunction "VIN_1") (pintype "bidirectional"))
      (node (ref "U$605") (pin "4") (pinfunction "EN2_4") (pintype "bidirectional"))
    )
    (net (code "134") (name "VDD_5V_PERIPH") (class "Default")
      (node (ref "L201") (pin "P$1") (pinfunction "P$1_P$1") (pintype "bidirectional"))
      (node (ref "L202") (pin "P$1") (pinfunction "P$1_P$1") (pintype "bidirectional"))
      (node (ref "L203") (pin "P$1") (pinfunction "P$1_P$1") (pintype "bidirectional"))
      (node (ref "L4") (pin "P$1") (pinfunction "P$1_P$1") (pintype "bidirectional"))
      (node (ref "L402") (pin "P$1") (pinfunction "P$1_P$1") (pintype "bidirectional"))
      (node (ref "L403") (pin "P$1") (pinfunction "P$1_P$1") (pintype "bidirectional"))
      (node (ref "L5") (pin "P$1") (pinfunction "P$1_P$1") (pintype "bidirectional"))
      (node (ref "L7") (pin "P$1") (pinfunction "P$1_P$1") (pintype "bidirectional"))
      (node (ref "U$604") (pin "8") (pinfunction "OUT_8") (pintype "bidirectional"))
    )
    (net (code "135") (name "VDD_5V_SENS") (class "Default")
      (node (ref "R609") (pin "P$1") (pinfunction "1_P$1") (pintype "passive"))
      (node (ref "R610") (pin "P$1") (pinfunction "1_P$1") (pintype "passive"))
      (node (ref "U101") (pin "29") (pinfunction "PA4_29") (pintype "bidirectional"))
    )
    (net (code "136") (name "VDD_IN") (class "Default")
      (node (ref "C1") (pin "1") (pinfunction "1_1") (pintype "passive"))
      (node (ref "C12") (pin "P$1") (pinfunction "1_P$1") (pintype "passive"))
      (node (ref "D1") (pin "CATHODE") (pinfunction "C_CATHODE") (pintype "passive"))
      (node (ref "D2") (pin "C") (pinfunction "C_C") (pintype "passive"))
      (node (ref "D5") (pin "C") (pinfunction "C_C") (pintype "passive"))
      (node (ref "U$15") (pin "2") (pinfunction "VIN_2") (pintype "power_in"))
      (node (ref "U$15") (pin "3") (pinfunction "EN_3") (pintype "input"))
    )
    (net (code "137") (name "VDD_SERVO_SENS") (class "Default")
      (node (ref "R918") (pin "P$1") (pinfunction "1_P$1") (pintype "passive"))
      (node (ref "R919") (pin "P$2") (pinfunction "2_P$2") (pintype "passive"))
    )
    (net (code "138") (name "V_EXT") (class "Default")
      (node (ref "D5") (pin "A") (pinfunction "A_A") (pintype "passive"))
      (node (ref "JP5") (pin "1") (pinfunction "1_1") (pintype "passive"))
      (node (ref "R922") (pin "P$2") (pinfunction "2_P$2") (pintype "passive"))
    )
    (net (code "139") (name "V_SERVO") (class "Default")
      (node (ref "D2") (pin "A") (pinfunction "A_A") (pintype "passive"))
      (node (ref "J1") (pin "PWR_S1") (pinfunction "S_PWR_S1") (pintype "passive"))
      (node (ref "J1") (pin "PWR_S2") (pinfunction "S_PWR_S2") (pintype "passive"))
      (node (ref "J1") (pin "PWR_S3") (pinfunction "S_PWR_S3") (pintype "passive"))
      (node (ref "J1") (pin "PWR_S4") (pinfunction "S_PWR_S4") (pintype "passive"))
      (node (ref "J1") (pin "PWR_S5") (pinfunction "S_PWR_S5") (pintype "passive"))
      (node (ref "J1") (pin "PWR_S6") (pinfunction "S_PWR_S6") (pintype "passive"))
      (node (ref "J1") (pin "PWR_S7") (pinfunction "S_PWR_S7") (pintype "passive"))
      (node (ref "J1") (pin "PWR_S8") (pinfunction "S_PWR_S8") (pintype "passive"))
    )
    (net (code "140") (name "unconnected-(J203-4-PadP$4)") (class "Default")
      (node (ref "J203") (pin "P$4") (pinfunction "4_P$4") (pintype "passive"))
    )
    (net (code "141") (name "unconnected-(J203-5-PadP$5)") (class "Default")
      (node (ref "J203") (pin "P$5") (pinfunction "5_P$5") (pintype "passive"))
    )
    (net (code "142") (name "unconnected-(JX301A-S-Pad10)") (class "Default")
      (node (ref "JX301") (pin "10") (pinfunction "S_10") (pintype "passive"))
    )
    (net (code "143") (name "unconnected-(JX301F-S-Pad8)") (class "Default")
      (node (ref "JX301") (pin "8") (pinfunction "S_8") (pintype "passive"))
    )
    (net (code "144") (name "unconnected-(L3-PadP$1)") (class "Default")
      (node (ref "L3") (pin "P$1") (pinfunction "P$1_P$1") (pintype "bidirectional"))
    )
    (net (code "145") (name "unconnected-(L3A-P$2-PadP$16)") (class "Default")
      (node (ref "L3") (pin "P$16") (pinfunction "P$2_P$16") (pintype "bidirectional"))
    )
    (net (code "146") (name "unconnected-(L3B-P$1-PadP$2)") (class "Default")
      (node (ref "L3") (pin "P$2") (pinfunction "P$1_P$2") (pintype "bidirectional"))
    )
    (net (code "147") (name "unconnected-(L3B-P$2-PadP$15)") (class "Default")
      (node (ref "L3") (pin "P$15") (pinfunction "P$2_P$15") (pintype "bidirectional"))
    )
    (net (code "148") (name "unconnected-(L3G-P$1-PadP$7)") (class "Default")
      (node (ref "L3") (pin "P$7") (pinfunction "P$1_P$7") (pintype "bidirectional"))
    )
    (net (code "149") (name "unconnected-(L3G-P$2-PadP$10)") (class "Default")
      (node (ref "L3") (pin "P$10") (pinfunction "P$2_P$10") (pintype "bidirectional"))
    )
    (net (code "150") (name "unconnected-(L3H-P$1-PadP$8)") (class "Default")
      (node (ref "L3") (pin "P$8") (pinfunction "P$1_P$8") (pintype "bidirectional"))
    )
    (net (code "151") (name "unconnected-(L3H-P$2-PadP$9)") (class "Default")
      (node (ref "L3") (pin "P$9") (pinfunction "P$2_P$9") (pintype "bidirectional"))
    )
    (net (code "152") (name "unconnected-(L6C-P$1-PadP$3)") (class "Default")
      (node (ref "L6") (pin "P$3") (pinfunction "P$1_P$3") (pintype "bidirectional"))
    )
    (net (code "153") (name "unconnected-(L6C-P$2-PadP$14)") (class "Default")
      (node (ref "L6") (pin "P$14") (pinfunction "P$2_P$14") (pintype "bidirectional"))
    )
    (net (code "154") (name "unconnected-(L6D-P$1-PadP$4)") (class "Default")
      (node (ref "L6") (pin "P$4") (pinfunction "P$1_P$4") (pintype "bidirectional"))
    )
    (net (code "155") (name "unconnected-(L6D-P$2-PadP$13)") (class "Default")
      (node (ref "L6") (pin "P$13") (pinfunction "P$2_P$13") (pintype "bidirectional"))
    )
    (net (code "156") (name "unconnected-(L6E-P$1-PadP$5)") (class "Default")
      (node (ref "L6") (pin "P$5") (pinfunction "P$1_P$5") (pintype "bidirectional"))
    )
    (net (code "157") (name "unconnected-(L6E-P$2-PadP$12)") (class "Default")
      (node (ref "L6") (pin "P$12") (pinfunction "P$2_P$12") (pintype "bidirectional"))
    )
    (net (code "158") (name "unconnected-(L6F-P$1-PadP$6)") (class "Default")
      (node (ref "L6") (pin "P$6") (pinfunction "P$1_P$6") (pintype "bidirectional"))
    )
    (net (code "159") (name "unconnected-(L6F-P$2-PadP$11)") (class "Default")
      (node (ref "L6") (pin "P$11") (pinfunction "P$2_P$11") (pintype "bidirectional"))
    )
    (net (code "160") (name "unconnected-(U$2-DSYNC-Pad12)") (class "Default")
      (node (ref "U$2") (pin "12") (pinfunction "DSYNC_12") (pintype "bidirectional"))
    )
    (net (code "161") (name "unconnected-(U$2-MST_SCL-Pad2)") (class "Default")
      (node (ref "U$2") (pin "2") (pinfunction "MST_SCL_2") (pintype "bidirectional"))
    )
    (net (code "162") (name "unconnected-(U$2-MST_SDA-Pad3)") (class "Default")
      (node (ref "U$2") (pin "3") (pinfunction "MST_SDA_3") (pintype "bidirectional"))
    )
    (net (code "163") (name "unconnected-(U$2-RSV3-Pad16)") (class "Default")
      (node (ref "U$2") (pin "16") (pinfunction "RSV3_16") (pintype "no_connect"))
    )
    (net (code "164") (name "unconnected-(U$15-FB-Pad12)") (class "Default")
      (node (ref "U$15") (pin "12") (pinfunction "FB_12") (pintype "input"))
    )
    (net (code "165") (name "unconnected-(U$15-PG-Pad5)") (class "Default")
      (node (ref "U$15") (pin "5") (pinfunction "PG_5") (pintype "output"))
    )
    (net (code "166") (name "unconnected-(U101I-PC0-Pad15)") (class "Default")
      (node (ref "U101") (pin "15") (pinfunction "PC0_15") (pintype "bidirectional"))
    )
    (net (code "167") (name "unconnected-(U101I-PC1-Pad16)") (class "Default")
      (node (ref "U101") (pin "16") (pinfunction "PC1_16") (pintype "bidirectional"))
    )
    (net (code "168") (name "unconnected-(U101I-PC2-Pad17)") (class "Default")
      (node (ref "U101") (pin "17") (pinfunction "PC2_17") (pintype "bidirectional"))
    )
    (net (code "169") (name "unconnected-(U101I-PC5-Pad34)") (class "Default")
      (node (ref "U101") (pin "34") (pinfunction "PC5_34") (pintype "bidirectional"))
    )
    (net (code "170") (name "unconnected-(U101I-PC6-Pad63)") (class "Default")
      (node (ref "U101") (pin "63") (pinfunction "PC6_63") (pintype "bidirectional"))
    )
    (net (code "171") (name "unconnected-(U101I-PC7-Pad64)") (class "Default")
      (node (ref "U101") (pin "64") (pinfunction "PC7_64") (pintype "bidirectional"))
    )
    (net (code "172") (name "unconnected-(U101L-PE10-Pad41)") (class "Default")
      (node (ref "U101") (pin "41") (pinfunction "PE10_41") (pintype "bidirectional"))
    )
    (net (code "173") (name "~{ACCEL_MAG_CS}") (class "Default")
      (node (ref "U101") (pin "9") (pinfunction "PC15_9") (pintype "bidirectional"))
    )
    (net (code "174") (name "~{BARO_CS}") (class "Default")
      (node (ref "U101") (pin "88") (pinfunction "PD7_88") (pintype "bidirectional"))
    )
    (net (code "175") (name "~{EX_VDD_5V_VALID}") (class "Default")
      (node (ref "U101") (pin "91") (pinfunction "PB5_91") (pintype "bidirectional"))
    )
    (net (code "176") (name "~{FMU-LED_AMBER}") (class "Default")
      (node (ref "R707") (pin "P$1") (pinfunction "1_P$1") (pintype "passive"))
      (node (ref "U101") (pin "43") (pinfunction "PE12_43") (pintype "bidirectional"))
    )
    (net (code "177") (name "~{FRAM_CS}") (class "Default")
      (node (ref "U101") (pin "57") (pinfunction "PD10_57") (pintype "bidirectional"))
    )
    (net (code "178") (name "~{GYRO_CS}") (class "Default")
      (node (ref "U$2") (pin "8") (pinfunction "CS_8") (pintype "bidirectional"))
      (node (ref "U101") (pin "7") (pinfunction "PC13_7") (pintype "bidirectional"))
    )
    (net (code "179") (name "~{SPI_EXT_NSS}") (class "Default")
      (node (ref "J403") (pin "P$5") (pinfunction "5_P$5") (pintype "passive"))
      (node (ref "U101") (pin "3") (pinfunction "PE4_3") (pintype "bidirectional"))
    )
    (net (code "180") (name "~{VDD_5V_PERIPH_EN}") (class "Default")
      (node (ref "R607") (pin "P$2") (pinfunction "2_P$2") (pintype "passive"))
      (node (ref "U$604") (pin "5") (pinfunction "~{CE}_5") (pintype "bidirectional"))
      (node (ref "U101") (pin "67") (pinfunction "PA8_67") (pintype "bidirectional"))
    )
    (net (code "181") (name "~{VDD_5V_PERIPH_OC}") (class "Default")
      (node (ref "U$604") (pin "4") (pinfunction "~{FAULT}_4") (pintype "bidirectional"))
      (node (ref "U101") (pin "46") (pinfunction "PE15_46") (pintype "bidirectional"))
    )
    (net (code "182") (name "~{VDD_SERVO_VALID}") (class "Default")
      (node (ref "U101") (pin "93") (pinfunction "PB7_93") (pintype "bidirectional"))
    )
  )
)
